# plaits_v50.net
KiCad netlist of a schematic drawn in EAGLE
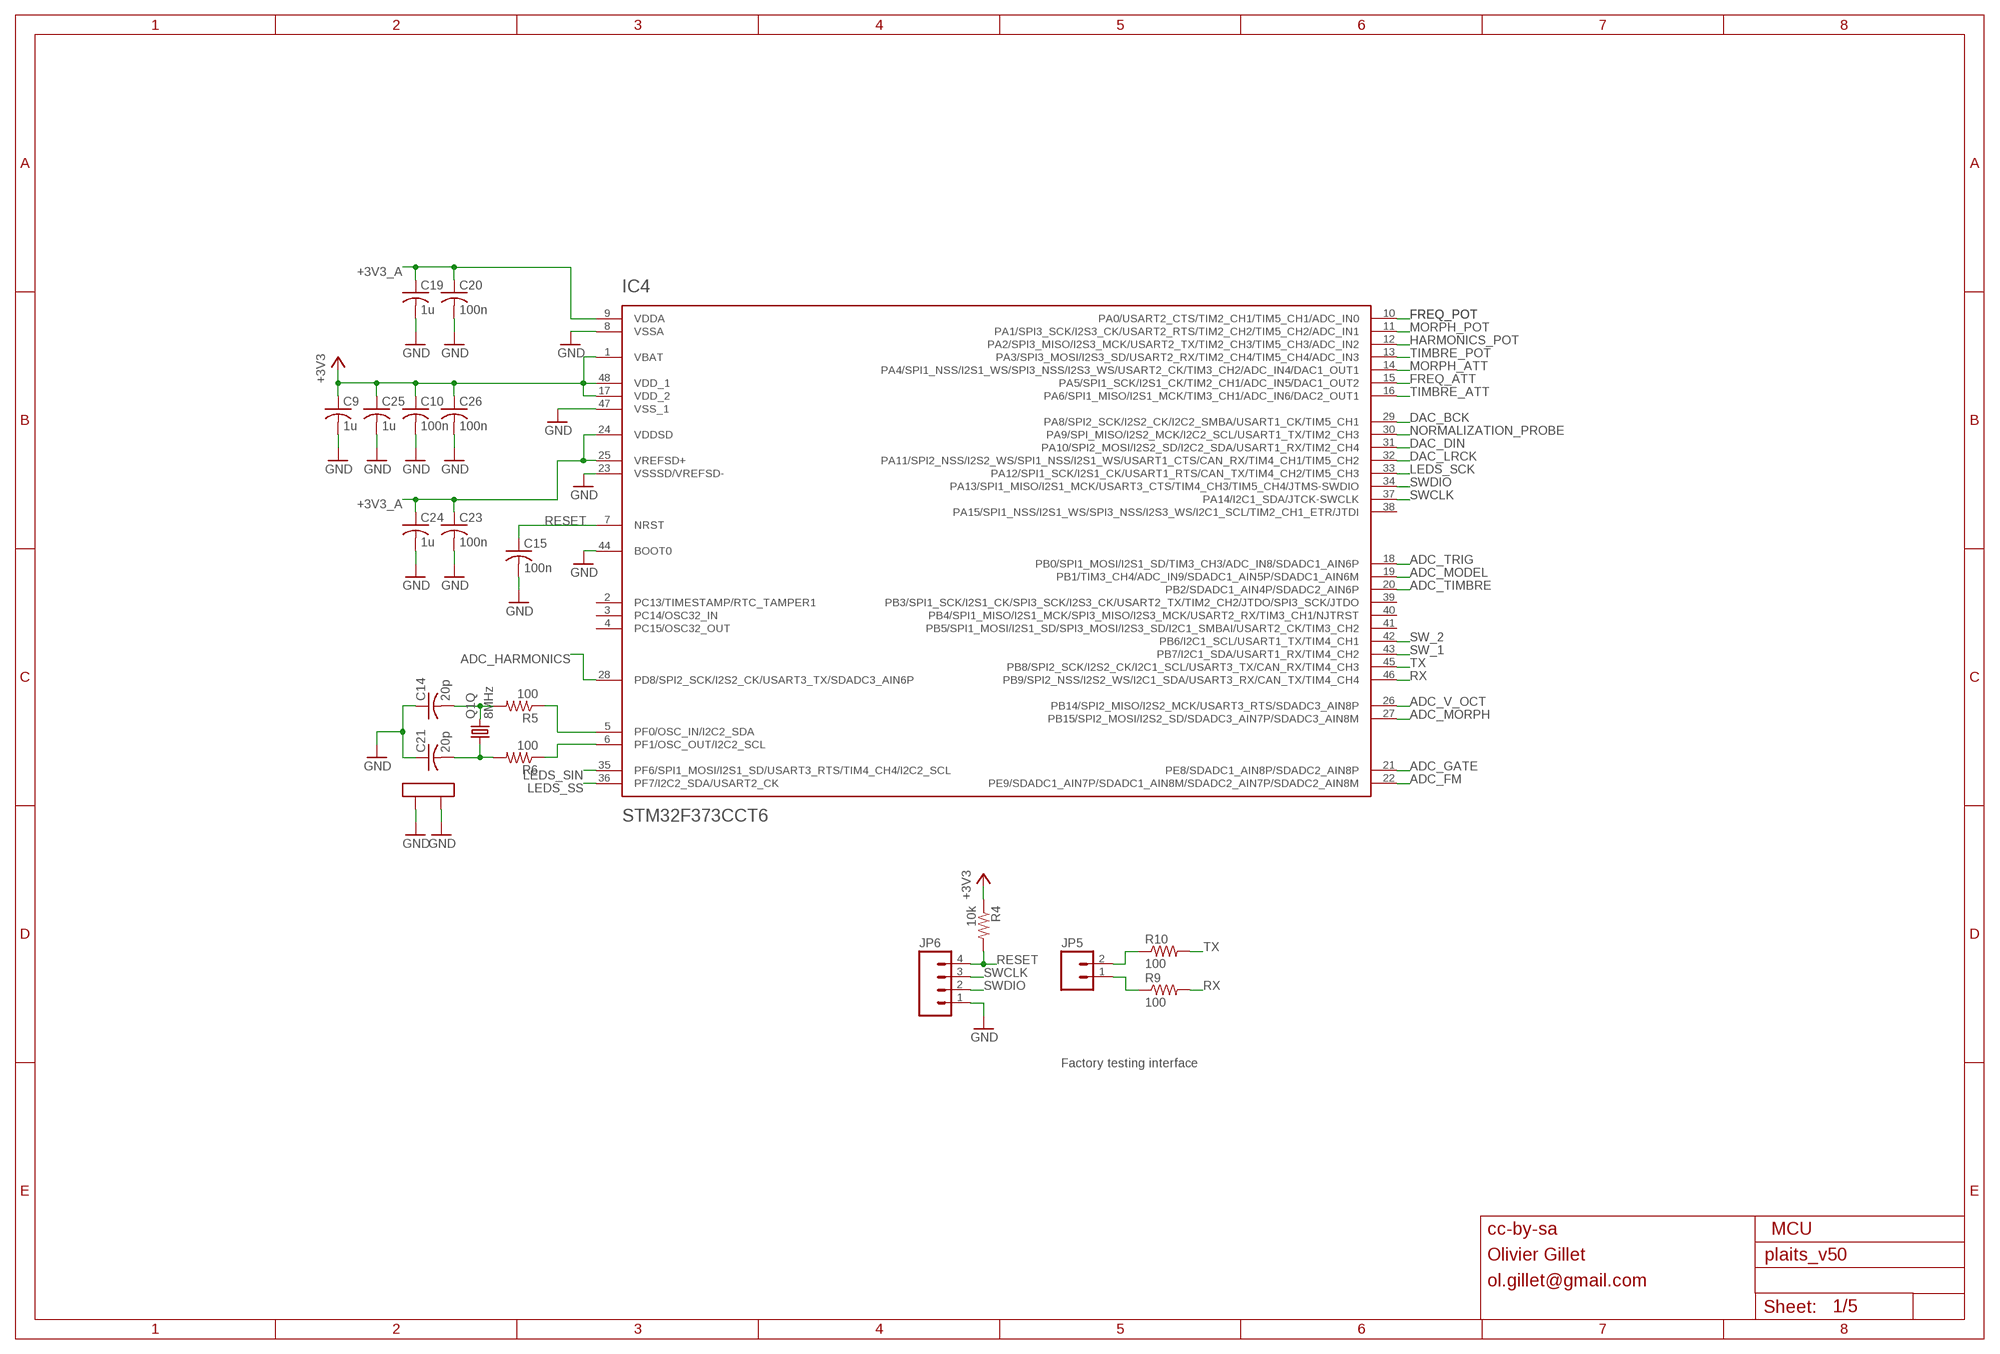
[diagram p0: schematic, sheet 1]
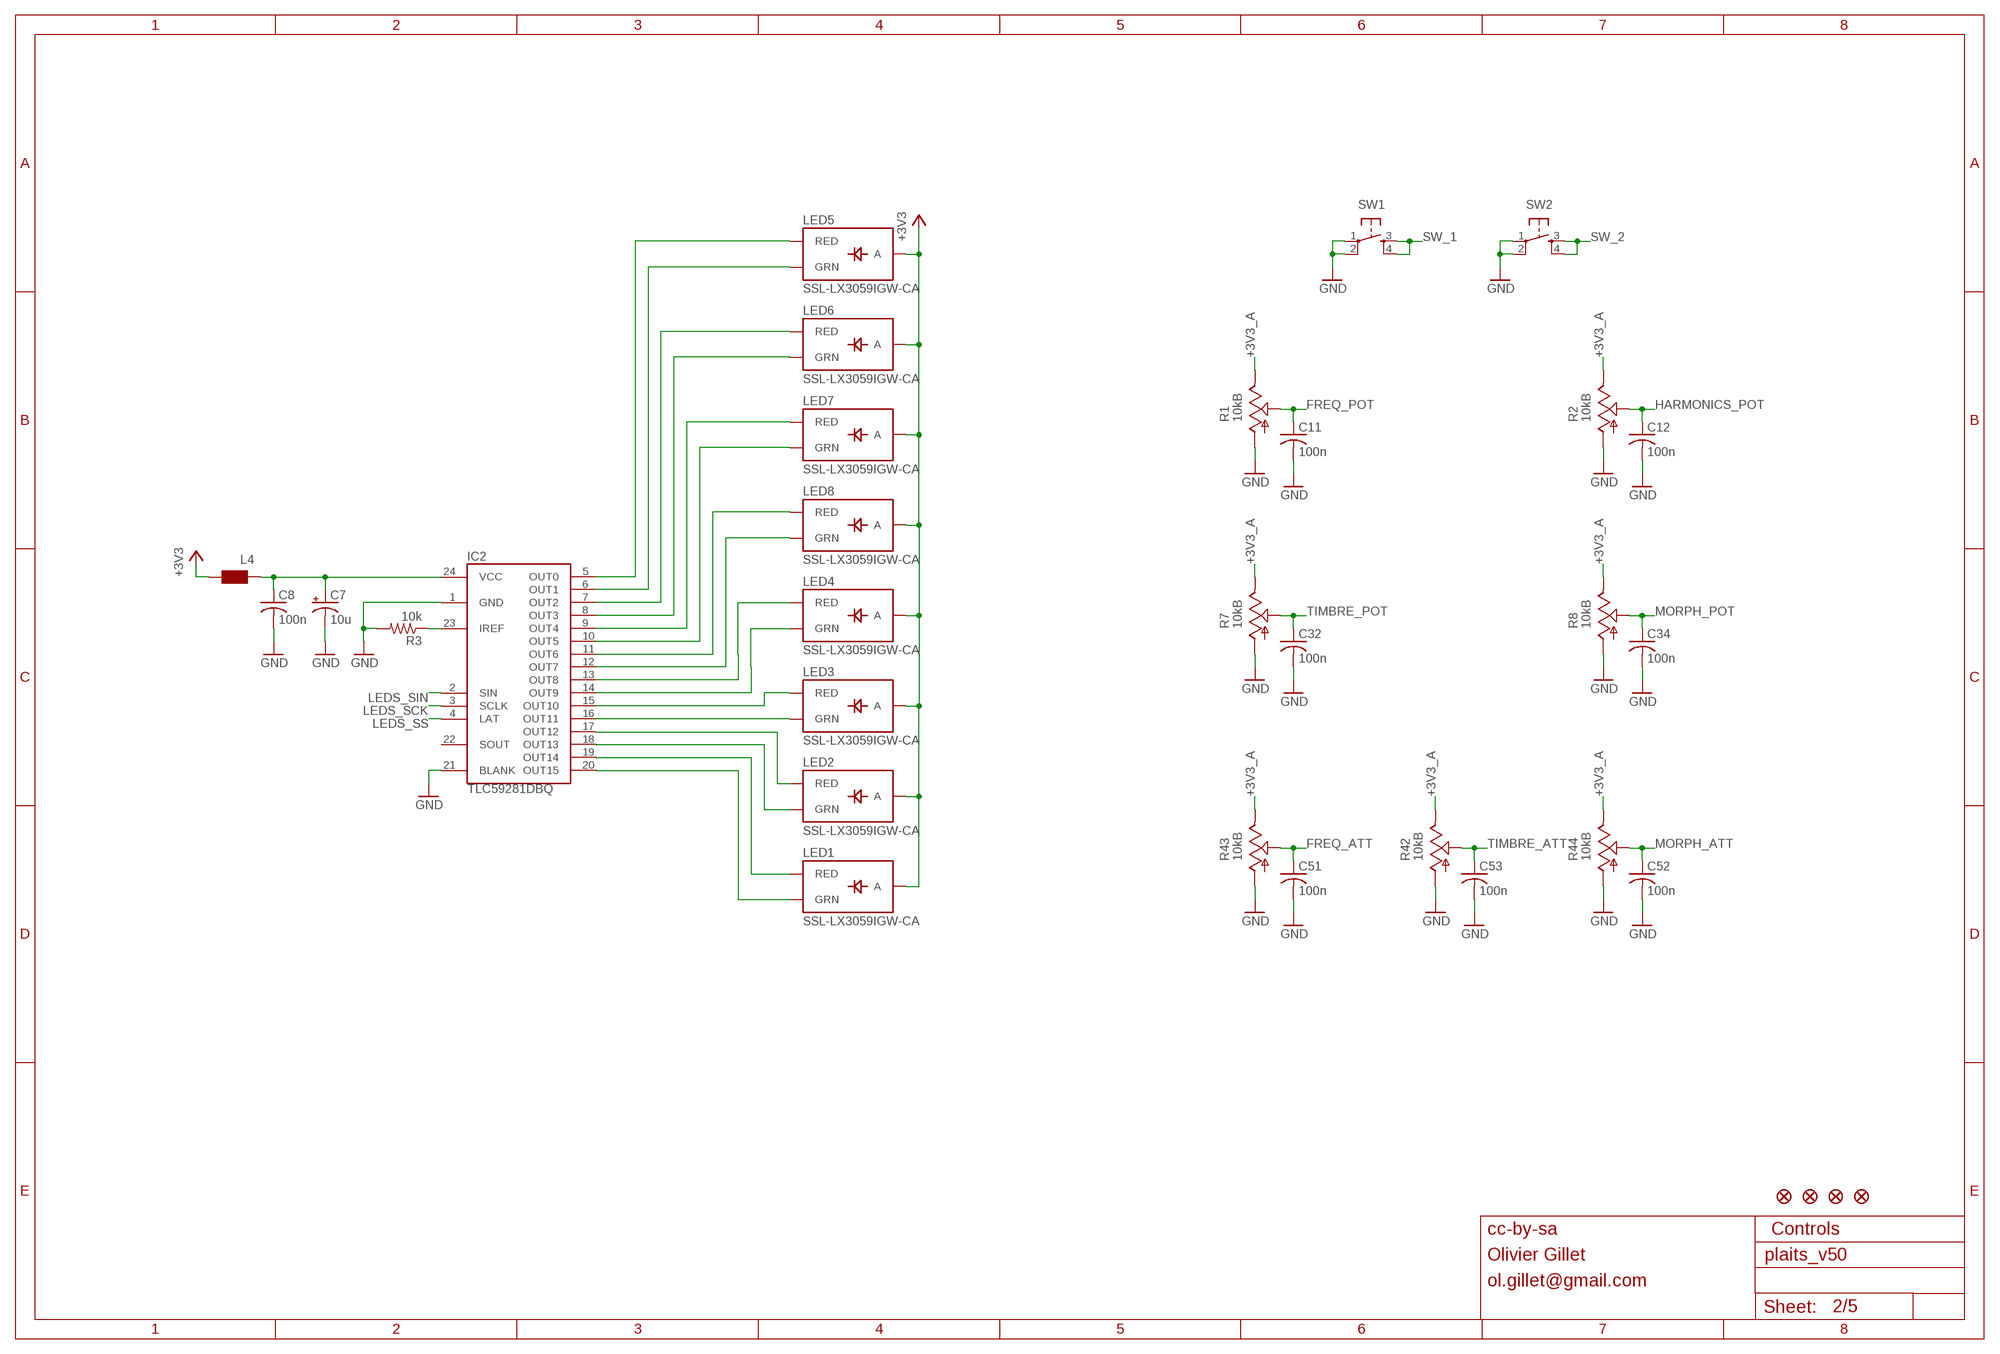
[diagram p1: schematic, sheet 2]
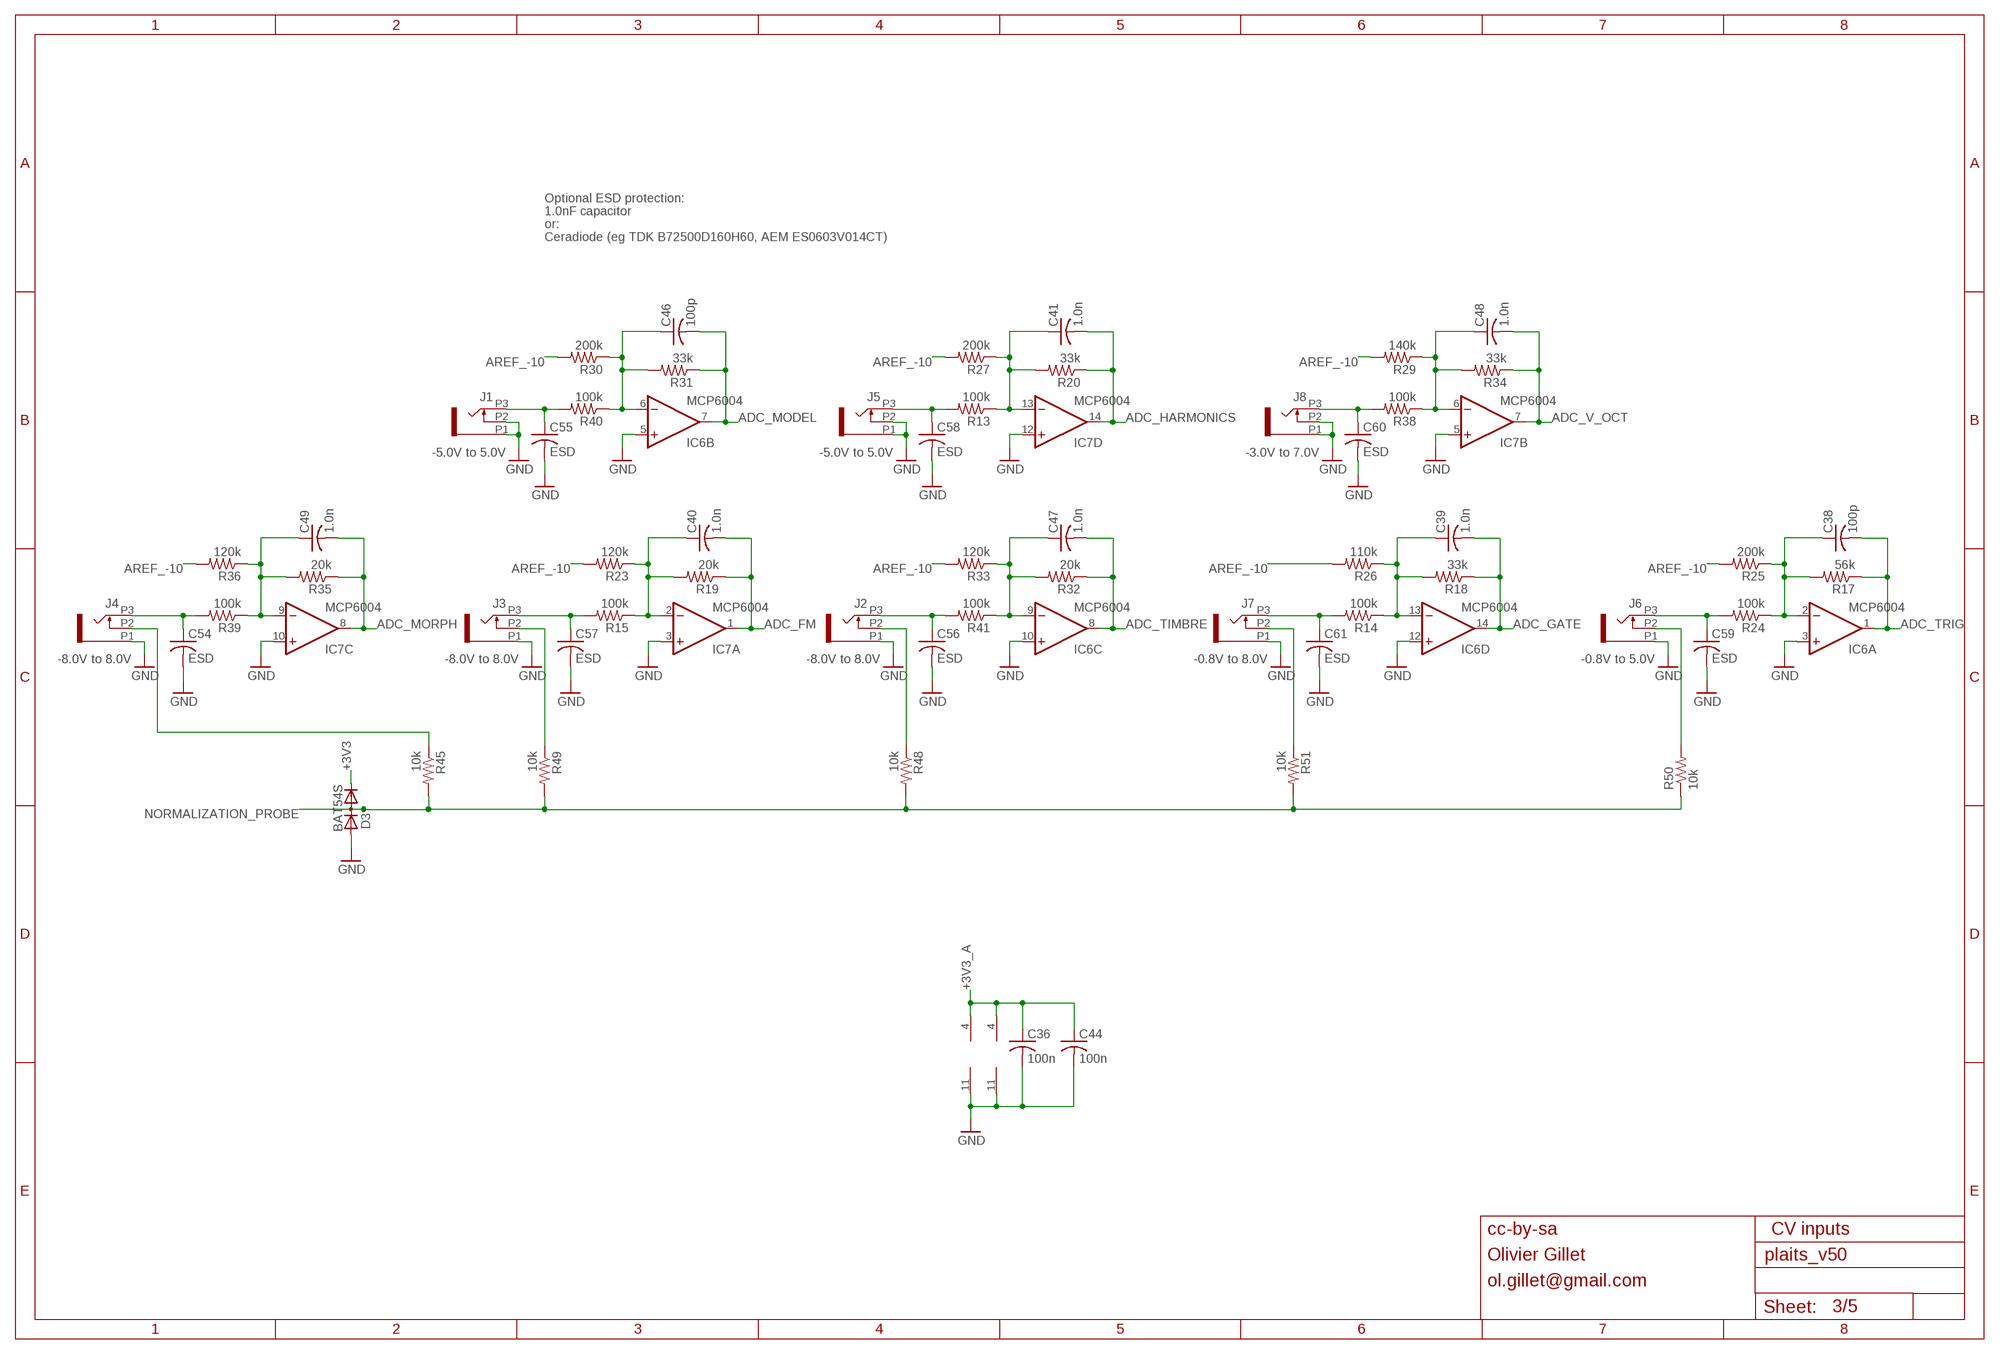
[diagram p2: schematic, sheet 3]
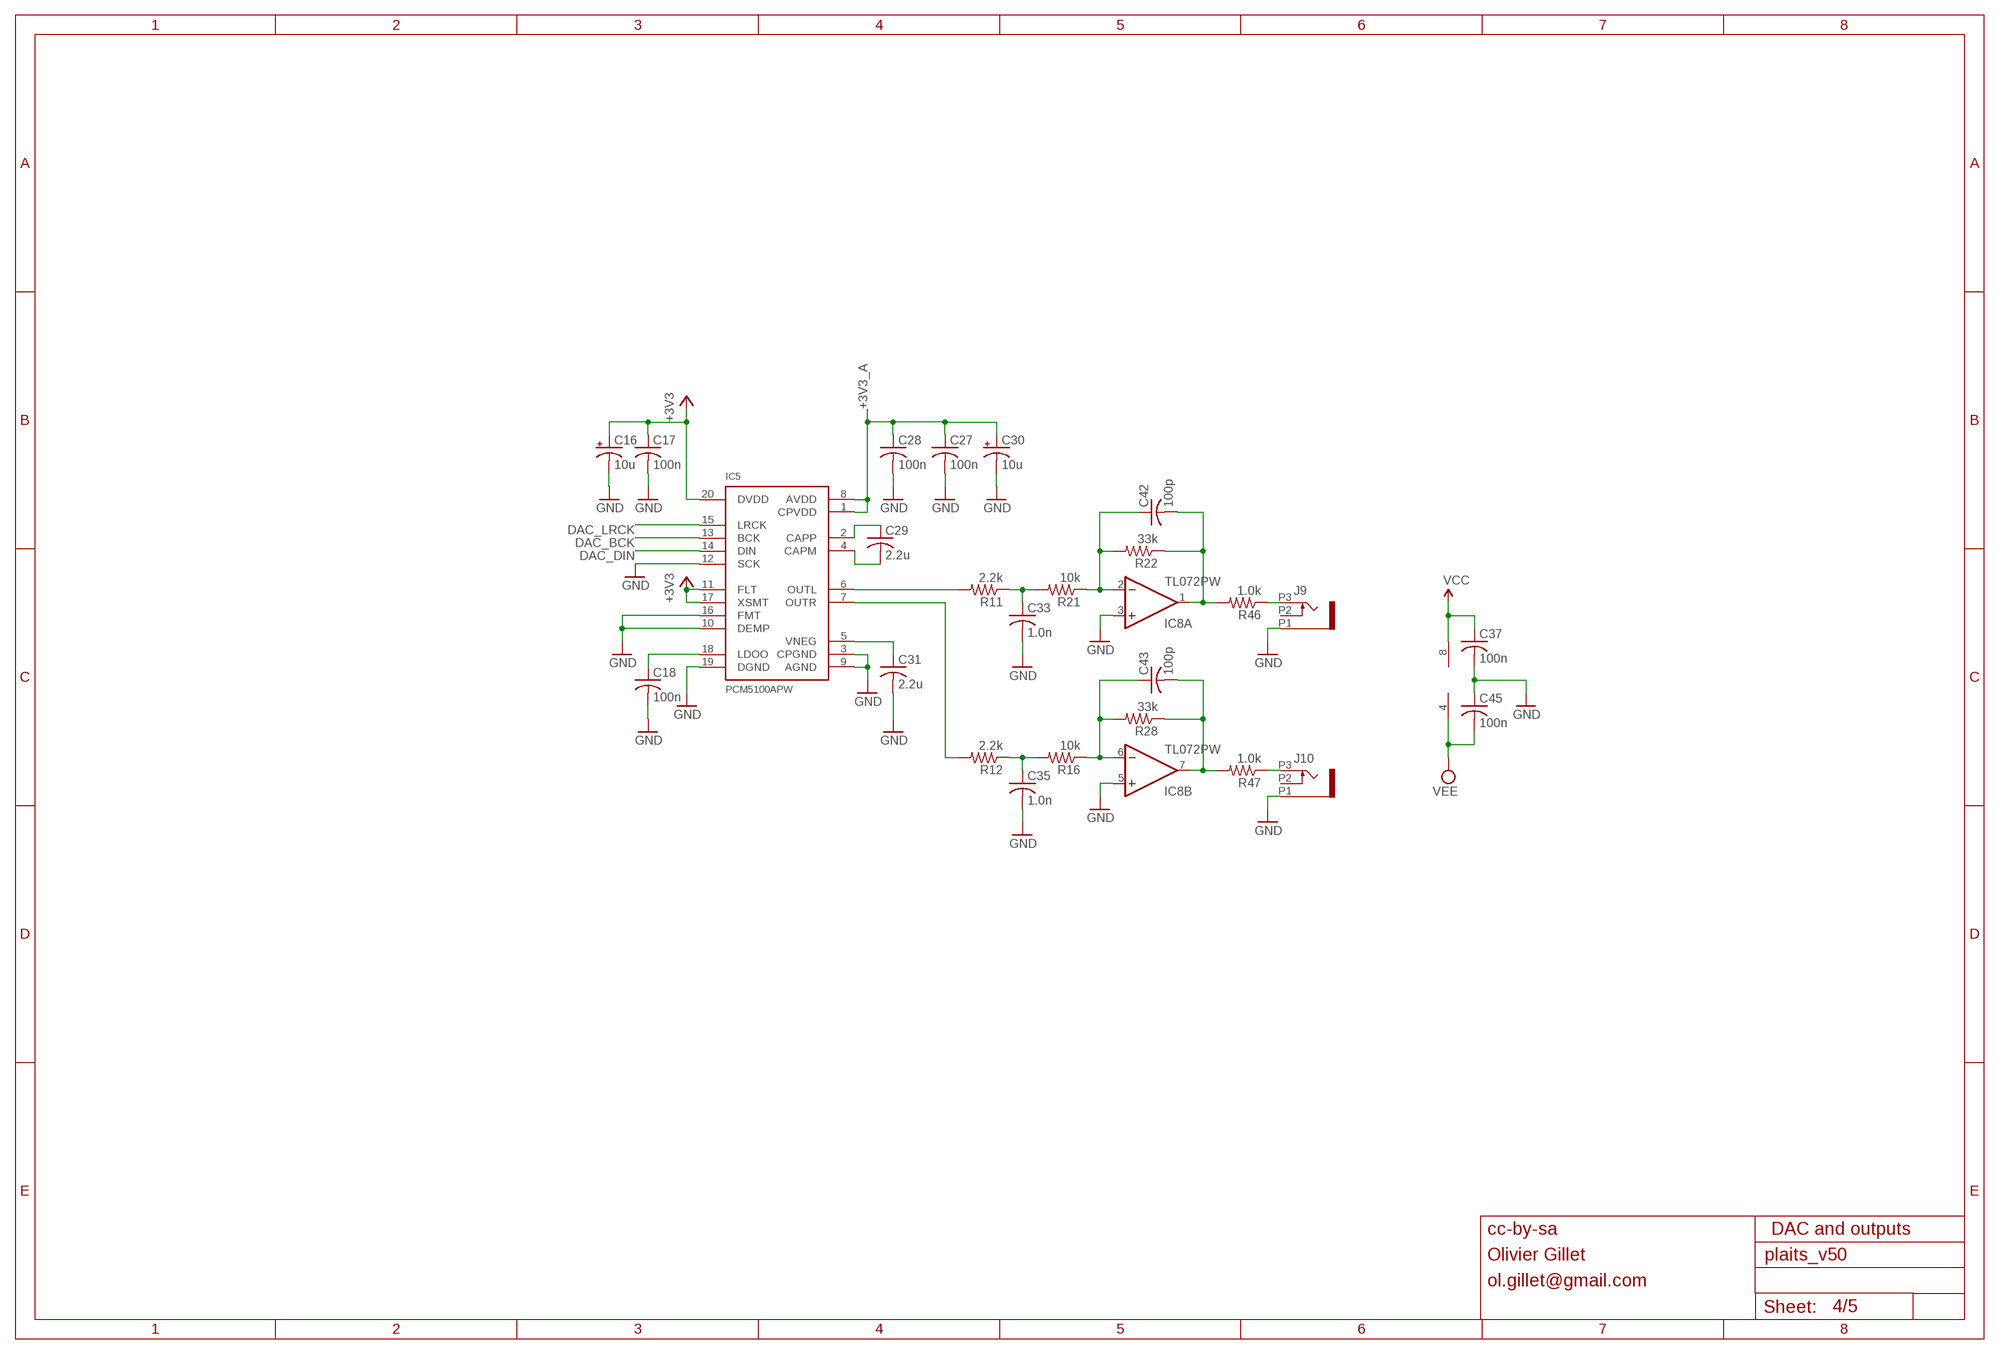
[diagram p3: schematic, sheet 4]
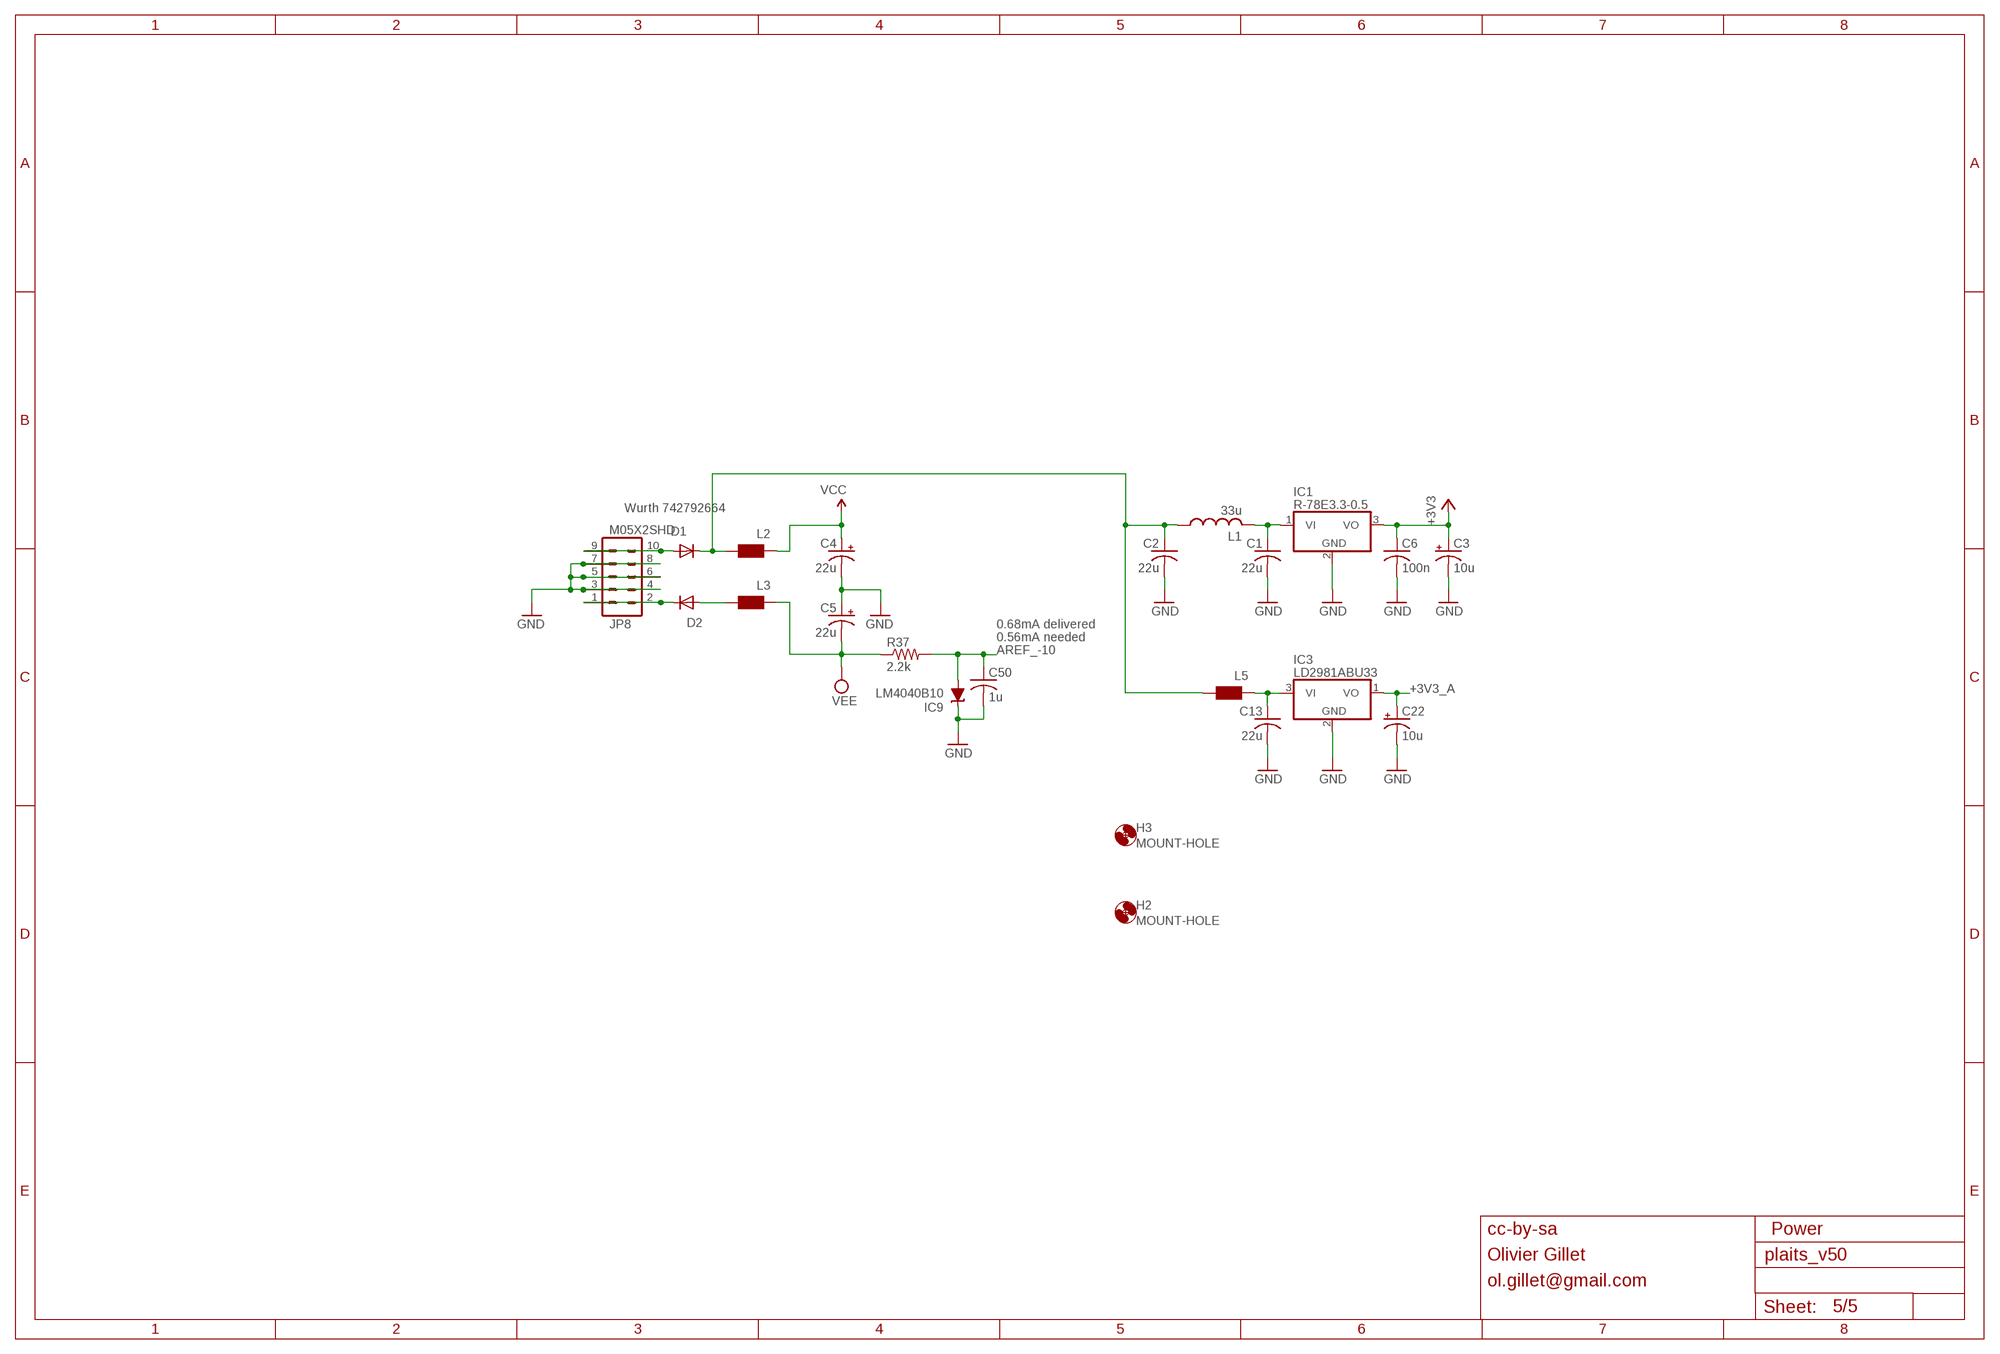
[diagram p4: schematic, sheet 5]

(export (version "E")
  (design (tool "Eeschema 10.0.6"))
  (components
    (comp (ref "C36")
      (value "100n")
      (footprint "eagle-import:C0603K")
      (libsource (lib "eagle-import") (part "rcl_334_C-USC0603K"))
    )
    (comp (ref "C38")
      (value "100p")
      (footprint "eagle-import:C0603K")
      (libsource (lib "eagle-import") (part "C-USC0603K"))
    )
    (comp (ref "C39")
      (value "1.0n")
      (footprint "eagle-import:C0603K")
      (libsource (lib "eagle-import") (part "C-USC0603K"))
    )
    (comp (ref "C40")
      (value "1.0n")
      (footprint "eagle-import:C0603K")
      (libsource (lib "eagle-import") (part "C-USC0603K"))
    )
    (comp (ref "C41")
      (value "1.0n")
      (footprint "eagle-import:C0603K")
      (libsource (lib "eagle-import") (part "C-USC0603K"))
    )
    (comp (ref "C44")
      (value "100n")
      (footprint "eagle-import:C0603K")
      (libsource (lib "eagle-import") (part "C-USC0603K"))
    )
    (comp (ref "C46")
      (value "100p")
      (footprint "eagle-import:C0603K")
      (libsource (lib "eagle-import") (part "C-USC0603K"))
    )
    (comp (ref "C47")
      (value "1.0n")
      (footprint "eagle-import:C0603K")
      (libsource (lib "eagle-import") (part "C-USC0603K"))
    )
    (comp (ref "C48")
      (value "1.0n")
      (footprint "eagle-import:C0603K")
      (libsource (lib "eagle-import") (part "C-USC0603K"))
    )
    (comp (ref "C49")
      (value "1.0n")
      (footprint "eagle-import:C0603K")
      (libsource (lib "eagle-import") (part "rcl_334_C-USC0603K"))
    )
    (comp (ref "C54")
      (value "ESD")
      (footprint "eagle-import:C0603K")
      (libsource (lib "eagle-import") (part "rcl_334_C-USC0603K"))
    )
    (comp (ref "C55")
      (value "ESD")
      (footprint "eagle-import:C0603K")
      (libsource (lib "eagle-import") (part "C-USC0603K"))
    )
    (comp (ref "C56")
      (value "ESD")
      (footprint "eagle-import:C0603")
      (libsource (lib "eagle-import") (part "C-USC0603"))
    )
    (comp (ref "C57")
      (value "ESD")
      (footprint "eagle-import:C0603K")
      (libsource (lib "eagle-import") (part "C-USC0603K"))
    )
    (comp (ref "C58")
      (value "ESD")
      (footprint "eagle-import:C0603K")
      (libsource (lib "eagle-import") (part "C-USC0603K"))
    )
    (comp (ref "C59")
      (value "ESD")
      (footprint "eagle-import:C0603K")
      (libsource (lib "eagle-import") (part "C-USC0603K"))
    )
    (comp (ref "C60")
      (value "ESD")
      (footprint "eagle-import:C0603K")
      (libsource (lib "eagle-import") (part "C-USC0603K"))
    )
    (comp (ref "C61")
      (value "ESD")
      (footprint "eagle-import:C0603K")
      (libsource (lib "eagle-import") (part "C-USC0603K"))
    )
    (comp (ref "D3")
      (value "BAT54S")
      (footprint "eagle-import:SOT23")
      (libsource (lib "eagle-import") (part "DIODE_2CACA-SOT23"))
    )
    (comp (ref "IC6")
      (value "MCP6004")
      (footprint "eagle-import:TSSOP14_065")
      (libsource (lib "eagle-import") (part "TL074PW"))
    )
    (comp (ref "IC7")
      (value "MCP6004")
      (footprint "eagle-import:TSSOP14_065")
      (libsource (lib "eagle-import") (part "TL074PW"))
    )
    (comp (ref "J1")
      (value "PJ301_THONKICONN6")
      (footprint "eagle-import:WQP_PJ_301M6")
      (libsource (lib "eagle-import") (part "PJ301_THONKICONN6"))
    )
    (comp (ref "J2")
      (value "PJ301_THONKICONN6")
      (footprint "eagle-import:WQP_PJ_301M6")
      (libsource (lib "eagle-import") (part "PJ301_THONKICONN6"))
    )
    (comp (ref "J3")
      (value "PJ301_THONKICONN6")
      (footprint "eagle-import:WQP_PJ_301M6")
      (libsource (lib "eagle-import") (part "PJ301_THONKICONN6"))
    )
    (comp (ref "J4")
      (value "PJ301_THONKICONN6")
      (footprint "eagle-import:WQP_PJ_301M6")
      (libsource (lib "eagle-import") (part "PJ301_THONKICONN6"))
    )
    (comp (ref "J5")
      (value "PJ301_THONKICONN6")
      (footprint "eagle-import:WQP_PJ_301M6")
      (libsource (lib "eagle-import") (part "PJ301_THONKICONN6"))
    )
    (comp (ref "J6")
      (value "PJ301_THONKICONN6")
      (footprint "eagle-import:WQP_PJ_301M6")
      (libsource (lib "eagle-import") (part "PJ301_THONKICONN6"))
    )
    (comp (ref "J7")
      (value "PJ301_THONKICONN6")
      (footprint "eagle-import:WQP_PJ_301M6")
      (libsource (lib "eagle-import") (part "PJ301_THONKICONN6"))
    )
    (comp (ref "J8")
      (value "PJ301_THONKICONN6")
      (footprint "eagle-import:WQP_PJ_301M6")
      (libsource (lib "eagle-import") (part "PJ301_THONKICONN6"))
    )
    (comp (ref "R13")
      (value "100k")
      (footprint "eagle-import:R0603")
      (libsource (lib "eagle-import") (part "R-US_R0603"))
    )
    (comp (ref "R14")
      (value "100k")
      (footprint "eagle-import:R0603")
      (libsource (lib "eagle-import") (part "R-US_R0603"))
    )
    (comp (ref "R15")
      (value "100k")
      (footprint "eagle-import:R0603")
      (libsource (lib "eagle-import") (part "R-US_R0603"))
    )
    (comp (ref "R17")
      (value "56k")
      (footprint "eagle-import:R0603")
      (libsource (lib "eagle-import") (part "R-US_R0603"))
    )
    (comp (ref "R18")
      (value "33k")
      (footprint "eagle-import:R0603")
      (libsource (lib "eagle-import") (part "R-US_R0603"))
    )
    (comp (ref "R19")
      (value "20k")
      (footprint "eagle-import:R0603")
      (libsource (lib "eagle-import") (part "R-US_R0603"))
    )
    (comp (ref "R20")
      (value "33k")
      (footprint "eagle-import:R0603")
      (libsource (lib "eagle-import") (part "R-US_R0603"))
    )
    (comp (ref "R23")
      (value "120k")
      (footprint "eagle-import:R0603")
      (libsource (lib "eagle-import") (part "R-US_R0603"))
    )
    (comp (ref "R24")
      (value "100k")
      (footprint "eagle-import:R0603")
      (libsource (lib "eagle-import") (part "R-US_R0603"))
    )
    (comp (ref "R25")
      (value "200k")
      (footprint "eagle-import:R0603")
      (libsource (lib "eagle-import") (part "R-US_R0603"))
    )
    (comp (ref "R26")
      (value "110k")
      (footprint "eagle-import:R0603")
      (libsource (lib "eagle-import") (part "R-US_R0603"))
    )
    (comp (ref "R27")
      (value "200k")
      (footprint "eagle-import:R0603")
      (libsource (lib "eagle-import") (part "R-US_R0603"))
    )
    (comp (ref "R29")
      (value "140k")
      (footprint "eagle-import:R0603")
      (libsource (lib "eagle-import") (part "R-US_R0603"))
    )
    (comp (ref "R30")
      (value "200k")
      (footprint "eagle-import:R0603")
      (libsource (lib "eagle-import") (part "R-US_R0603"))
    )
    (comp (ref "R31")
      (value "33k")
      (footprint "eagle-import:R0603")
      (libsource (lib "eagle-import") (part "R-US_R0603"))
    )
    (comp (ref "R32")
      (value "20k")
      (footprint "eagle-import:R0603")
      (libsource (lib "eagle-import") (part "R-US_R0603"))
    )
    (comp (ref "R33")
      (value "120k")
      (footprint "eagle-import:R0603")
      (libsource (lib "eagle-import") (part "R-US_R0603"))
    )
    (comp (ref "R34")
      (value "33k")
      (footprint "eagle-import:R0603")
      (libsource (lib "eagle-import") (part "R-US_R0603"))
    )
    (comp (ref "R35")
      (value "20k")
      (footprint "eagle-import:R0603")
      (libsource (lib "eagle-import") (part "R-US_R0603"))
    )
    (comp (ref "R36")
      (value "120k")
      (footprint "eagle-import:R0603")
      (libsource (lib "eagle-import") (part "R-US_R0603"))
    )
    (comp (ref "R38")
      (value "100k")
      (footprint "eagle-import:R0603")
      (libsource (lib "eagle-import") (part "rcl_334_R-US_R0603"))
    )
    (comp (ref "R39")
      (value "100k")
      (footprint "eagle-import:R0603")
      (libsource (lib "eagle-import") (part "rcl_334_R-US_R0603"))
    )
    (comp (ref "R40")
      (value "100k")
      (footprint "eagle-import:R0603")
      (libsource (lib "eagle-import") (part "R-US_R0603"))
    )
    (comp (ref "R41")
      (value "100k")
      (footprint "eagle-import:R0603")
      (libsource (lib "eagle-import") (part "R-US_R0603"))
    )
    (comp (ref "R45")
      (value "10k")
      (footprint "eagle-import:R0603")
      (libsource (lib "eagle-import") (part "R-US_R0603"))
    )
    (comp (ref "R48")
      (value "10k")
      (footprint "eagle-import:R0603")
      (libsource (lib "eagle-import") (part "rcl_334_R-US_R0603"))
    )
    (comp (ref "R49")
      (value "10k")
      (footprint "eagle-import:R0603")
      (libsource (lib "eagle-import") (part "R-US_R0603"))
    )
    (comp (ref "R50")
      (value "10k")
      (footprint "eagle-import:R0603")
      (libsource (lib "eagle-import") (part "R-US_R0603"))
    )
    (comp (ref "R51")
      (value "10k")
      (footprint "eagle-import:R0603")
      (libsource (lib "eagle-import") (part "R-US_R0603"))
    )
    (comp (ref "C9")
      (value "1u")
      (footprint "eagle-import:C0603K")
      (libsource (lib "eagle-import") (part "C-USC0603K"))
    )
    (comp (ref "C10")
      (value "100n")
      (footprint "eagle-import:C0603K")
      (libsource (lib "eagle-import") (part "C-USC0603K"))
    )
    (comp (ref "C14")
      (value "20p")
      (footprint "eagle-import:C0603K")
      (libsource (lib "eagle-import") (part "C-USC0603K"))
    )
    (comp (ref "C15")
      (value "100n")
      (footprint "eagle-import:C0603K")
      (libsource (lib "eagle-import") (part "C-USC0603K"))
    )
    (comp (ref "C19")
      (value "1u")
      (footprint "eagle-import:C0603K")
      (libsource (lib "eagle-import") (part "rcl_334_C-USC0603K"))
    )
    (comp (ref "C20")
      (value "100n")
      (footprint "eagle-import:C0603K")
      (libsource (lib "eagle-import") (part "C-USC0603K"))
    )
    (comp (ref "C21")
      (value "20p")
      (footprint "eagle-import:C0603K")
      (libsource (lib "eagle-import") (part "C-USC0603K"))
    )
    (comp (ref "C23")
      (value "100n")
      (footprint "eagle-import:C0603K")
      (libsource (lib "eagle-import") (part "C-USC0603K"))
    )
    (comp (ref "C24")
      (value "1u")
      (footprint "eagle-import:C0603K")
      (libsource (lib "eagle-import") (part "C-USC0603K"))
    )
    (comp (ref "C25")
      (value "1u")
      (footprint "eagle-import:C0603K")
      (libsource (lib "eagle-import") (part "C-USC0603K"))
    )
    (comp (ref "C26")
      (value "100n")
      (footprint "eagle-import:C0603K")
      (libsource (lib "eagle-import") (part "C-USC0603K"))
    )
    (comp (ref "IC4")
      (value "STM32F373CCT6")
      (footprint "eagle-import:LQFP48")
      (libsource (lib "eagle-import") (part "STM32F373C"))
    )
    (comp (ref "JP5")
      (value "M02PTH")
      (footprint "eagle-import:1X02")
      (libsource (lib "eagle-import") (part "M02PTH"))
    )
    (comp (ref "JP6")
      (value "M04PTH")
      (footprint "eagle-import:1X04")
      (libsource (lib "eagle-import") (part "M04PTH"))
    )
    (comp (ref "Q1")
      (value "8MHz")
      (footprint "eagle-import:CTS406")
      (libsource (lib "eagle-import") (part "CRYSTAL"))
    )
    (comp (ref "R4")
      (value "10k")
      (footprint "eagle-import:R0603")
      (libsource (lib "eagle-import") (part "R-US_R0603"))
    )
    (comp (ref "R5")
      (value "100")
      (footprint "eagle-import:R0603")
      (libsource (lib "eagle-import") (part "rcl_334_R-US_R0603"))
    )
    (comp (ref "R6")
      (value "100")
      (footprint "eagle-import:R0603")
      (libsource (lib "eagle-import") (part "R-US_R0603"))
    )
    (comp (ref "R9")
      (value "100")
      (footprint "eagle-import:R0603")
      (libsource (lib "eagle-import") (part "R-US_R0603"))
    )
    (comp (ref "R10")
      (value "100")
      (footprint "eagle-import:R0603")
      (libsource (lib "eagle-import") (part "R-US_R0603"))
    )
    (comp (ref "C7")
      (value "10u")
      (footprint "eagle-import:PANASONIC_A")
      (libsource (lib "eagle-import") (part "CPOL-USA"))
    )
    (comp (ref "C8")
      (value "100n")
      (footprint "eagle-import:C0603K")
      (libsource (lib "eagle-import") (part "rcl_334_C-USC0603K"))
    )
    (comp (ref "C11")
      (value "100n")
      (footprint "eagle-import:C0603K")
      (libsource (lib "eagle-import") (part "C-USC0603K"))
    )
    (comp (ref "C12")
      (value "100n")
      (footprint "eagle-import:C0603K")
      (libsource (lib "eagle-import") (part "C-USC0603K"))
    )
    (comp (ref "C32")
      (value "100n")
      (footprint "eagle-import:C0603K")
      (libsource (lib "eagle-import") (part "C-USC0603K"))
    )
    (comp (ref "C34")
      (value "100n")
      (footprint "eagle-import:C0603K")
      (libsource (lib "eagle-import") (part "C-USC0603K"))
    )
    (comp (ref "C51")
      (value "100n")
      (footprint "eagle-import:C0603K")
      (libsource (lib "eagle-import") (part "C-USC0603K"))
    )
    (comp (ref "C52")
      (value "100n")
      (footprint "eagle-import:C0603K")
      (libsource (lib "eagle-import") (part "C-USC0603K"))
    )
    (comp (ref "C53")
      (value "100n")
      (footprint "eagle-import:C0603K")
      (libsource (lib "eagle-import") (part "C-USC0603K"))
    )
    (comp (ref "IC2")
      (value "TLC59281DBQ")
      (footprint "eagle-import:TSSOP24_0635")
      (libsource (lib "eagle-import") (part "TLC59281DBQ"))
    )
    (comp (ref "JP1")
      (value "FIDUCIAL1X2")
      (footprint "eagle-import:FIDUCIAL-1X2")
      (libsource (lib "eagle-import") (part "FIDUCIAL1X2"))
    )
    (comp (ref "JP2")
      (value "FIDUCIAL1X2")
      (footprint "eagle-import:FIDUCIAL-1X2")
      (libsource (lib "eagle-import") (part "FIDUCIAL1X2"))
    )
    (comp (ref "JP3")
      (value "FIDUCIAL1X2")
      (footprint "eagle-import:FIDUCIAL-1X2")
      (libsource (lib "eagle-import") (part "FIDUCIAL1X2"))
    )
    (comp (ref "JP4")
      (value "FIDUCIAL1X2")
      (footprint "eagle-import:FIDUCIAL-1X2")
      (libsource (lib "eagle-import") (part "FIDUCIAL1X2"))
    )
    (comp (ref "L4")
      (value "WE-CBF_0603")
      (footprint "eagle-import:0603")
      (libsource (lib "eagle-import") (part "WE-CBF_0603"))
    )
    (comp (ref "LED1")
      (value "SSL-LX3059IGW-CA")
      (footprint "eagle-import:LED-BICOLOR-THROUGHHOLE-LUMEX")
      (libsource (lib "eagle-import") (part "LED-BICOLOR-THROUGHHOLE-CA"))
    )
    (comp (ref "LED2")
      (value "SSL-LX3059IGW-CA")
      (footprint "eagle-import:LED-BICOLOR-THROUGHHOLE-LUMEX")
      (libsource (lib "eagle-import") (part "LED-BICOLOR-THROUGHHOLE-CA"))
    )
    (comp (ref "LED3")
      (value "SSL-LX3059IGW-CA")
      (footprint "eagle-import:LED-BICOLOR-THROUGHHOLE-LUMEX")
      (libsource (lib "eagle-import") (part "LED-BICOLOR-THROUGHHOLE-CA"))
    )
    (comp (ref "LED4")
      (value "SSL-LX3059IGW-CA")
      (footprint "eagle-import:LED-BICOLOR-THROUGHHOLE-LUMEX")
      (libsource (lib "eagle-import") (part "LED-BICOLOR-THROUGHHOLE-CA"))
    )
    (comp (ref "LED5")
      (value "SSL-LX3059IGW-CA")
      (footprint "eagle-import:LED-BICOLOR-THROUGHHOLE-LUMEX")
      (libsource (lib "eagle-import") (part "LED-BICOLOR-THROUGHHOLE-CA"))
    )
    (comp (ref "LED6")
      (value "SSL-LX3059IGW-CA")
      (footprint "eagle-import:LED-BICOLOR-THROUGHHOLE-LUMEX")
      (libsource (lib "eagle-import") (part "LED-BICOLOR-THROUGHHOLE-CA"))
    )
    (comp (ref "LED7")
      (value "SSL-LX3059IGW-CA")
      (footprint "eagle-import:LED-BICOLOR-THROUGHHOLE-LUMEX")
      (libsource (lib "eagle-import") (part "LED-BICOLOR-THROUGHHOLE-CA"))
    )
    (comp (ref "LED8")
      (value "SSL-LX3059IGW-CA")
      (footprint "eagle-import:LED-BICOLOR-THROUGHHOLE-LUMEX")
      (libsource (lib "eagle-import") (part "LED-BICOLOR-THROUGHHOLE-CA"))
    )
    (comp (ref "R1")
      (value "10kB")
      (footprint "eagle-import:ALPS_POT_VERTICAL_PS")
      (libsource (lib "eagle-import") (part "POT_USVERTICAL_PS"))
    )
    (comp (ref "R2")
      (value "10kB")
      (footprint "eagle-import:ALPS_POT_VERTICAL_PS")
      (libsource (lib "eagle-import") (part "POT_USVERTICAL_PS"))
    )
    (comp (ref "R3")
      (value "10k")
      (footprint "eagle-import:R0603")
      (libsource (lib "eagle-import") (part "rcl_334_R-US_R0603"))
    )
    (comp (ref "R7")
      (value "10kB")
      (footprint "eagle-import:ALPS_POT_VERTICAL_PS")
      (libsource (lib "eagle-import") (part "POT_USVERTICAL_PS"))
    )
    (comp (ref "R8")
      (value "10kB")
      (footprint "eagle-import:ALPS_POT_VERTICAL_PS")
      (libsource (lib "eagle-import") (part "POT_USVERTICAL_PS"))
    )
    (comp (ref "R42")
      (value "10kB")
      (footprint "eagle-import:ALPS_POT_VERTICAL")
      (libsource (lib "eagle-import") (part "POT_USVERTICAL"))
    )
    (comp (ref "R43")
      (value "10kB")
      (footprint "eagle-import:ALPS_POT_VERTICAL")
      (libsource (lib "eagle-import") (part "POT_USVERTICAL"))
    )
    (comp (ref "R44")
      (value "10kB")
      (footprint "eagle-import:ALPS_POT_VERTICAL")
      (libsource (lib "eagle-import") (part "POT_USVERTICAL"))
    )
    (comp (ref "SW1")
      (value "TAC_SWITCHPTH")
      (footprint "eagle-import:TACTILE-PTH")
      (libsource (lib "eagle-import") (part "TAC_SWITCHPTH"))
    )
    (comp (ref "SW2")
      (value "TAC_SWITCHPTH")
      (footprint "eagle-import:TACTILE-PTH")
      (libsource (lib "eagle-import") (part "TAC_SWITCHPTH"))
    )
    (comp (ref "C1")
      (value "22u")
      (footprint "eagle-import:C1206")
      (libsource (lib "eagle-import") (part "C-USC1206"))
    )
    (comp (ref "C2")
      (value "22u")
      (footprint "eagle-import:C1206")
      (libsource (lib "eagle-import") (part "C-USC1206"))
    )
    (comp (ref "C3")
      (value "10u")
      (footprint "eagle-import:PANASONIC_A")
      (libsource (lib "eagle-import") (part "CPOL-USA"))
    )
    (comp (ref "C4")
      (value "22u")
      (footprint "eagle-import:PANASONIC_B")
      (libsource (lib "eagle-import") (part "CPOL-USB"))
    )
    (comp (ref "C5")
      (value "22u")
      (footprint "eagle-import:PANASONIC_B")
      (libsource (lib "eagle-import") (part "CPOL-USB"))
    )
    (comp (ref "C6")
      (value "100n")
      (footprint "eagle-import:C0603K")
      (libsource (lib "eagle-import") (part "rcl_334_C-USC0603K"))
    )
    (comp (ref "C13")
      (value "22u")
      (footprint "eagle-import:C1206")
      (libsource (lib "eagle-import") (part "C-USC1206"))
    )
    (comp (ref "C22")
      (value "10u")
      (footprint "eagle-import:PANASONIC_A")
      (libsource (lib "eagle-import") (part "CPOL-USA"))
    )
    (comp (ref "C50")
      (value "1u")
      (footprint "eagle-import:C0603K")
      (libsource (lib "eagle-import") (part "rcl_334_C-USC0603K"))
    )
    (comp (ref "D1")
      (value "1N5819HW")
      (footprint "eagle-import:SOD123")
      (libsource (lib "eagle-import") (part "DIODE-SOD123"))
    )
    (comp (ref "D2")
      (value "1N5819HW")
      (footprint "eagle-import:SOD123")
      (libsource (lib "eagle-import") (part "DIODE-SOD123"))
    )
    (comp (ref "H2")
      (value "MOUNT-HOLE")
      (footprint "eagle-import:3,0TINY")
      (libsource (lib "eagle-import") (part "MOUNT-HOLE3.0TINY"))
    )
    (comp (ref "H3")
      (value "MOUNT-HOLE")
      (footprint "eagle-import:3,0TINY")
      (libsource (lib "eagle-import") (part "MOUNT-HOLE3.0TINY"))
    )
    (comp (ref "IC1")
      (value "R-78E3.3-0.5")
      (footprint "eagle-import:WE78")
      (libsource (lib "eagle-import") (part "WE173950378"))
    )
    (comp (ref "IC3")
      (value "LD2981ABU33")
      (footprint "eagle-import:SOT89")
      (libsource (lib "eagle-import") (part "LD2981ABU"))
    )
    (comp (ref "IC9")
      (value "LM4040B10")
      (footprint "eagle-import:DBZ_R-PDSO-G3")
      (libsource (lib "eagle-import") (part "LM4041DBZB12"))
    )
    (comp (ref "JP8")
      (value "M05X2SHD")
      (footprint "eagle-import:2X5-SHROUDED")
      (libsource (lib "eagle-import") (part "M05X2SHD"))
    )
    (comp (ref "L1")
      (value "33u")
      (footprint "eagle-import:L2012C")
      (libsource (lib "eagle-import") (part "L-USL2012C"))
    )
    (comp (ref "L2")
      (value "WE-CBF_0603")
      (footprint "eagle-import:0603")
      (libsource (lib "eagle-import") (part "WE-CBF_0603"))
    )
    (comp (ref "L3")
      (value "WE-CBF_0603")
      (footprint "eagle-import:0603")
      (libsource (lib "eagle-import") (part "WE-CBF_0603"))
    )
    (comp (ref "L5")
      (value "WE-CBF_0603")
      (footprint "eagle-import:0603")
      (libsource (lib "eagle-import") (part "WE-CBF_0603"))
    )
    (comp (ref "R37")
      (value "2.2k")
      (footprint "eagle-import:R0603")
      (libsource (lib "eagle-import") (part "rcl_334_R-US_R0603"))
    )
    (comp (ref "C16")
      (value "10u")
      (footprint "eagle-import:PANASONIC_A")
      (libsource (lib "eagle-import") (part "CPOL-USA"))
    )
    (comp (ref "C17")
      (value "100n")
      (footprint "eagle-import:C0603K")
      (libsource (lib "eagle-import") (part "rcl_334_C-USC0603K"))
    )
    (comp (ref "C18")
      (value "100n")
      (footprint "eagle-import:C0603K")
      (libsource (lib "eagle-import") (part "rcl_334_C-USC0603K"))
    )
    (comp (ref "C27")
      (value "100n")
      (footprint "eagle-import:C0603K")
      (libsource (lib "eagle-import") (part "rcl_334_C-USC0603K"))
    )
    (comp (ref "C28")
      (value "100n")
      (footprint "eagle-import:C0603K")
      (libsource (lib "eagle-import") (part "C-USC0603K"))
    )
    (comp (ref "C29")
      (value "2.2u")
      (footprint "eagle-import:C0805")
      (libsource (lib "eagle-import") (part "C-USC0805"))
    )
    (comp (ref "C30")
      (value "10u")
      (footprint "eagle-import:PANASONIC_A")
      (libsource (lib "eagle-import") (part "CPOL-USA"))
    )
    (comp (ref "C31")
      (value "2.2u")
      (footprint "eagle-import:C0805")
      (libsource (lib "eagle-import") (part "C-USC0805"))
    )
    (comp (ref "C33")
      (value "1.0n")
      (footprint "eagle-import:C0603K")
      (libsource (lib "eagle-import") (part "C-USC0603K"))
    )
    (comp (ref "C35")
      (value "1.0n")
      (footprint "eagle-import:C0603K")
      (libsource (lib "eagle-import") (part "C-USC0603K"))
    )
    (comp (ref "C37")
      (value "100n")
      (footprint "eagle-import:C0603K")
      (libsource (lib "eagle-import") (part "C-USC0603K"))
    )
    (comp (ref "C42")
      (value "100p")
      (footprint "eagle-import:C0603K")
      (libsource (lib "eagle-import") (part "C-USC0603K"))
    )
    (comp (ref "C43")
      (value "100p")
      (footprint "eagle-import:C0603K")
      (libsource (lib "eagle-import") (part "C-USC0603K"))
    )
    (comp (ref "C45")
      (value "100n")
      (footprint "eagle-import:C0603K")
      (libsource (lib "eagle-import") (part "C-USC0603K"))
    )
    (comp (ref "IC5")
      (value "PCM5100APW")
      (footprint "eagle-import:SSOP20")
      (libsource (lib "eagle-import") (part "PCM5100PW"))
    )
    (comp (ref "IC8")
      (value "TL072PW")
      (footprint "eagle-import:TSSOP08")
      (libsource (lib "eagle-import") (part "TL072PW"))
    )
    (comp (ref "J9")
      (value "PJ301_THONKICONN6")
      (footprint "eagle-import:WQP_PJ_301M6")
      (libsource (lib "eagle-import") (part "PJ301_THONKICONN6"))
    )
    (comp (ref "J10")
      (value "PJ301_THONKICONN6")
      (footprint "eagle-import:WQP_PJ_301M6")
      (libsource (lib "eagle-import") (part "PJ301_THONKICONN6"))
    )
    (comp (ref "R11")
      (value "2.2k")
      (footprint "eagle-import:R0603")
      (libsource (lib "eagle-import") (part "R-US_R0603"))
    )
    (comp (ref "R12")
      (value "2.2k")
      (footprint "eagle-import:R0603")
      (libsource (lib "eagle-import") (part "R-US_R0603"))
    )
    (comp (ref "R16")
      (value "10k")
      (footprint "eagle-import:R0603")
      (libsource (lib "eagle-import") (part "R-US_R0603"))
    )
    (comp (ref "R21")
      (value "10k")
      (footprint "eagle-import:R0603")
      (libsource (lib "eagle-import") (part "R-US_R0603"))
    )
    (comp (ref "R22")
      (value "33k")
      (footprint "eagle-import:R0603")
      (libsource (lib "eagle-import") (part "rcl_334_R-US_R0603"))
    )
    (comp (ref "R28")
      (value "33k")
      (footprint "eagle-import:R0603")
      (libsource (lib "eagle-import") (part "R-US_R0603"))
    )
    (comp (ref "R46")
      (value "1.0k")
      (footprint "eagle-import:R0603")
      (libsource (lib "eagle-import") (part "R-US_R0603"))
    )
    (comp (ref "R47")
      (value "1.0k")
      (footprint "eagle-import:R0603")
      (libsource (lib "eagle-import") (part "R-US_R0603"))
    )
  )
  (nets
    (net (code "1") (name "+3V3") (class "Default")
      (node (ref "C10") (pin "1") (pinfunction "1_1") (pintype "passive"))
      (node (ref "C16") (pin "+") (pinfunction "+_+") (pintype "passive"))
      (node (ref "C17") (pin "1") (pinfunction "1_1") (pintype "passive"))
      (node (ref "C25") (pin "1") (pinfunction "1_1") (pintype "passive"))
      (node (ref "C26") (pin "1") (pinfunction "1_1") (pintype "passive"))
      (node (ref "C3") (pin "+") (pinfunction "+_+") (pintype "passive"))
      (node (ref "C6") (pin "1") (pinfunction "1_1") (pintype "passive"))
      (node (ref "C9") (pin "1") (pinfunction "1_1") (pintype "passive"))
      (node (ref "D3") (pin "2") (pinfunction "C_2") (pintype "passive"))
      (node (ref "IC1") (pin "3") (pinfunction "VO_3") (pintype "passive"))
      (node (ref "IC4") (pin "1") (pinfunction "VBAT_1") (pintype "power_in"))
      (node (ref "IC4") (pin "17") (pinfunction "VDD_2_17") (pintype "power_in"))
      (node (ref "IC4") (pin "48") (pinfunction "VDD_1_48") (pintype "power_in"))
      (node (ref "IC5") (pin "11") (pinfunction "FLT_11") (pintype "input"))
      (node (ref "IC5") (pin "17") (pinfunction "XSMT_17") (pintype "input"))
      (node (ref "IC5") (pin "20") (pinfunction "DVDD_20") (pintype "power_in"))
      (node (ref "L4") (pin "2") (pinfunction "2_2") (pintype "passive"))
      (node (ref "LED1") (pin "A") (pinfunction "A_A") (pintype "bidirectional"))
      (node (ref "LED2") (pin "A") (pinfunction "A_A") (pintype "bidirectional"))
      (node (ref "LED3") (pin "A") (pinfunction "A_A") (pintype "bidirectional"))
      (node (ref "LED4") (pin "A") (pinfunction "A_A") (pintype "bidirectional"))
      (node (ref "LED5") (pin "A") (pinfunction "A_A") (pintype "bidirectional"))
      (node (ref "LED6") (pin "A") (pinfunction "A_A") (pintype "bidirectional"))
      (node (ref "LED7") (pin "A") (pinfunction "A_A") (pintype "bidirectional"))
      (node (ref "LED8") (pin "A") (pinfunction "A_A") (pintype "bidirectional"))
      (node (ref "R4") (pin "1") (pinfunction "1_1") (pintype "passive"))
    )
    (net (code "2") (name "+3V3_A") (class "Default")
      (node (ref "C19") (pin "1") (pinfunction "1_1") (pintype "passive"))
      (node (ref "C20") (pin "1") (pinfunction "1_1") (pintype "passive"))
      (node (ref "C22") (pin "+") (pinfunction "+_+") (pintype "passive"))
      (node (ref "C23") (pin "1") (pinfunction "1_1") (pintype "passive"))
      (node (ref "C24") (pin "1") (pinfunction "1_1") (pintype "passive"))
      (node (ref "C27") (pin "1") (pinfunction "1_1") (pintype "passive"))
      (node (ref "C28") (pin "1") (pinfunction "1_1") (pintype "passive"))
      (node (ref "C30") (pin "+") (pinfunction "+_+") (pintype "passive"))
      (node (ref "C36") (pin "1") (pinfunction "1_1") (pintype "passive"))
      (node (ref "C44") (pin "1") (pinfunction "1_1") (pintype "passive"))
      (node (ref "IC3") (pin "1") (pinfunction "VO_1") (pintype "passive"))
      (node (ref "IC4") (pin "24") (pinfunction "VDDSD_24") (pintype "power_in"))
      (node (ref "IC4") (pin "25") (pinfunction "VREFSD+_25") (pintype "power_in"))
      (node (ref "IC4") (pin "9") (pinfunction "VDDA_9") (pintype "power_in"))
      (node (ref "IC5") (pin "1") (pinfunction "CPVDD_1") (pintype "bidirectional"))
      (node (ref "IC5") (pin "8") (pinfunction "AVDD_8") (pintype "power_in"))
      (node (ref "IC6") (pin "4") (pinfunction "V+_4") (pintype "power_in"))
      (node (ref "IC7") (pin "4") (pinfunction "V+_4") (pintype "power_in"))
      (node (ref "R1") (pin "P$1") (pinfunction "E_P$1") (pintype "passive"))
      (node (ref "R2") (pin "P$1") (pinfunction "E_P$1") (pintype "passive"))
      (node (ref "R42") (pin "P$1") (pinfunction "E_P$1") (pintype "passive"))
      (node (ref "R43") (pin "P$1") (pinfunction "E_P$1") (pintype "passive"))
      (node (ref "R44") (pin "P$1") (pinfunction "E_P$1") (pintype "passive"))
      (node (ref "R7") (pin "P$1") (pinfunction "E_P$1") (pintype "passive"))
      (node (ref "R8") (pin "P$1") (pinfunction "E_P$1") (pintype "passive"))
    )
    (net (code "3") (name "ADC_FM") (class "Default")
      (node (ref "C40") (pin "2") (pinfunction "2_2") (pintype "passive"))
      (node (ref "IC4") (pin "22") (pinfunction "PE9/SDADC1_AIN7P/SDADC1_AIN8M/SDADC2_AIN7P/SDADC2_AIN8M_22") (pintype "bidirectional"))
      (node (ref "IC7") (pin "1") (pinfunction "OUT_1") (pintype "output"))
      (node (ref "R19") (pin "1") (pinfunction "1_1") (pintype "passive"))
    )
    (net (code "4") (name "ADC_GATE") (class "Default")
      (node (ref "C39") (pin "2") (pinfunction "2_2") (pintype "passive"))
      (node (ref "IC4") (pin "21") (pinfunction "PE8/SDADC1_AIN8P/SDADC2_AIN8P_21") (pintype "bidirectional"))
      (node (ref "IC6") (pin "14") (pinfunction "OUT_14") (pintype "output"))
      (node (ref "R18") (pin "1") (pinfunction "1_1") (pintype "passive"))
    )
    (net (code "5") (name "ADC_HARMONICS") (class "Default")
      (node (ref "C41") (pin "2") (pinfunction "2_2") (pintype "passive"))
      (node (ref "IC4") (pin "28") (pinfunction "PD8/SPI2_SCK/I2S2_CK/USART3_TX/SDADC3_AIN6P_28") (pintype "bidirectional"))
      (node (ref "IC7") (pin "14") (pinfunction "OUT_14") (pintype "output"))
      (node (ref "R20") (pin "1") (pinfunction "1_1") (pintype "passive"))
    )
    (net (code "6") (name "ADC_MODEL") (class "Default")
      (node (ref "C46") (pin "2") (pinfunction "2_2") (pintype "passive"))
      (node (ref "IC4") (pin "19") (pinfunction "PB1/TIM3_CH4/ADC_IN9/SDADC1_AIN5P/SDADC1_AIN6M_19") (pintype "bidirectional"))
      (node (ref "IC6") (pin "7") (pinfunction "OUT_7") (pintype "output"))
      (node (ref "R31") (pin "1") (pinfunction "1_1") (pintype "passive"))
    )
    (net (code "7") (name "ADC_MORPH") (class "Default")
      (node (ref "C49") (pin "2") (pinfunction "2_2") (pintype "passive"))
      (node (ref "IC4") (pin "27") (pinfunction "PB15/SPI2_MOSI/I2S2_SD/SDADC3_AIN7P/SDADC3_AIN8M_27") (pintype "bidirectional"))
      (node (ref "IC7") (pin "8") (pinfunction "OUT_8") (pintype "output"))
      (node (ref "R35") (pin "1") (pinfunction "1_1") (pintype "passive"))
    )
    (net (code "8") (name "ADC_TIMBRE") (class "Default")
      (node (ref "C47") (pin "2") (pinfunction "2_2") (pintype "passive"))
      (node (ref "IC4") (pin "20") (pinfunction "PB2/SDADC1_AIN4P/SDADC2_AIN6P_20") (pintype "bidirectional"))
      (node (ref "IC6") (pin "8") (pinfunction "OUT_8") (pintype "output"))
      (node (ref "R32") (pin "1") (pinfunction "1_1") (pintype "passive"))
    )
    (net (code "9") (name "ADC_TRIG") (class "Default")
      (node (ref "C38") (pin "2") (pinfunction "2_2") (pintype "passive"))
      (node (ref "IC4") (pin "18") (pinfunction "PB0/SPI1_MOSI/I2S1_SD/TIM3_CH3/ADC_IN8/SDADC1_AIN6P_18") (pintype "bidirectional"))
      (node (ref "IC6") (pin "1") (pinfunction "OUT_1") (pintype "output"))
      (node (ref "R17") (pin "1") (pinfunction "1_1") (pintype "passive"))
    )
    (net (code "10") (name "ADC_V_OCT") (class "Default")
      (node (ref "C48") (pin "2") (pinfunction "2_2") (pintype "passive"))
      (node (ref "IC4") (pin "26") (pinfunction "PB14/SPI2_MISO/I2S2_MCK/USART3_RTS/SDADC3_AIN8P_26") (pintype "bidirectional"))
      (node (ref "IC7") (pin "7") (pinfunction "OUT_7") (pintype "output"))
      (node (ref "R34") (pin "1") (pinfunction "1_1") (pintype "passive"))
    )
    (net (code "11") (name "AREF_-10") (class "Default")
      (node (ref "C50") (pin "1") (pinfunction "1_1") (pintype "passive"))
      (node (ref "IC9") (pin "2") (pinfunction "A_2") (pintype "passive"))
      (node (ref "R23") (pin "2") (pinfunction "2_2") (pintype "passive"))
      (node (ref "R25") (pin "2") (pinfunction "2_2") (pintype "passive"))
      (node (ref "R26") (pin "2") (pinfunction "2_2") (pintype "passive"))
      (node (ref "R27") (pin "2") (pinfunction "2_2") (pintype "passive"))
      (node (ref "R29") (pin "2") (pinfunction "2_2") (pintype "passive"))
      (node (ref "R30") (pin "2") (pinfunction "2_2") (pintype "passive"))
      (node (ref "R33") (pin "2") (pinfunction "2_2") (pintype "passive"))
      (node (ref "R36") (pin "2") (pinfunction "2_2") (pintype "passive"))
      (node (ref "R37") (pin "2") (pinfunction "2_2") (pintype "passive"))
    )
    (net (code "12") (name "DAC_BCK") (class "Default")
      (node (ref "IC4") (pin "29") (pinfunction "PA8/SPI2_SCK/I2S2_CK/I2C2_SMBA/USART1_CK/TIM5_CH1_29") (pintype "bidirectional"))
      (node (ref "IC5") (pin "13") (pinfunction "BCK_13") (pintype "input"))
    )
    (net (code "13") (name "DAC_DIN") (class "Default")
      (node (ref "IC4") (pin "31") (pinfunction "PA10/SPI2_MOSI/I2S2_SD/I2C2_SDA/USART1_RX/TIM2_CH4_31") (pintype "bidirectional"))
      (node (ref "IC5") (pin "14") (pinfunction "DIN_14") (pintype "input"))
    )
    (net (code "14") (name "DAC_LRCK") (class "Default")
      (node (ref "IC4") (pin "32") (pinfunction "PA11/SPI2_NSS/I2S2_WS/SPI1_NSS/I2S1_WS/USART1_CTS/CAN_RX/TIM4_CH1/TIM5_CH2_32") (pintype "bidirectional"))
      (node (ref "IC5") (pin "15") (pinfunction "LRCK_15") (pintype "input"))
    )
    (net (code "15") (name "FREQ_ATT") (class "Default")
      (node (ref "C51") (pin "1") (pinfunction "1_1") (pintype "passive"))
      (node (ref "IC4") (pin "15") (pinfunction "PA5/SPI1_SCK/I2S1_CK/TIM2_CH1/ADC_IN5/DAC1_OUT2_15") (pintype "bidirectional"))
      (node (ref "R43") (pin "P$2") (pinfunction "S_P$2") (pintype "passive"))
    )
    (net (code "16") (name "FREQ_POT") (class "Default")
      (node (ref "C11") (pin "1") (pinfunction "1_1") (pintype "passive"))
      (node (ref "IC4") (pin "10") (pinfunction "PA0/USART2_CTS/TIM2_CH1/TIM5_CH1/ADC_IN0_10") (pintype "bidirectional"))
      (node (ref "R1") (pin "P$2") (pinfunction "S_P$2") (pintype "passive"))
    )
    (net (code "17") (name "GND") (class "Default")
      (node (ref "C1") (pin "2") (pinfunction "2_2") (pintype "passive"))
      (node (ref "C10") (pin "2") (pinfunction "2_2") (pintype "passive"))
      (node (ref "C11") (pin "2") (pinfunction "2_2") (pintype "passive"))
      (node (ref "C12") (pin "2") (pinfunction "2_2") (pintype "passive"))
      (node (ref "C13") (pin "2") (pinfunction "2_2") (pintype "passive"))
      (node (ref "C14") (pin "1") (pinfunction "1_1") (pintype "passive"))
      (node (ref "C15") (pin "2") (pinfunction "2_2") (pintype "passive"))
      (node (ref "C16") (pin "-") (pinfunction "-_-") (pintype "passive"))
      (node (ref "C17") (pin "2") (pinfunction "2_2") (pintype "passive"))
      (node (ref "C18") (pin "2") (pinfunction "2_2") (pintype "passive"))
      (node (ref "C19") (pin "2") (pinfunction "2_2") (pintype "passive"))
      (node (ref "C2") (pin "2") (pinfunction "2_2") (pintype "passive"))
      (node (ref "C20") (pin "2") (pinfunction "2_2") (pintype "passive"))
      (node (ref "C21") (pin "1") (pinfunction "1_1") (pintype "passive"))
      (node (ref "C22") (pin "-") (pinfunction "-_-") (pintype "passive"))
      (node (ref "C23") (pin "2") (pinfunction "2_2") (pintype "passive"))
      (node (ref "C24") (pin "2") (pinfunction "2_2") (pintype "passive"))
      (node (ref "C25") (pin "2") (pinfunction "2_2") (pintype "passive"))
      (node (ref "C26") (pin "2") (pinfunction "2_2") (pintype "passive"))
      (node (ref "C27") (pin "2") (pinfunction "2_2") (pintype "passive"))
      (node (ref "C28") (pin "2") (pinfunction "2_2") (pintype "passive"))
      (node (ref "C3") (pin "-") (pinfunction "-_-") (pintype "passive"))
      (node (ref "C30") (pin "-") (pinfunction "-_-") (pintype "passive"))
      (node (ref "C31") (pin "2") (pinfunction "2_2") (pintype "passive"))
      (node (ref "C32") (pin "2") (pinfunction "2_2") (pintype "passive"))
      (node (ref "C33") (pin "2") (pinfunction "2_2") (pintype "passive"))
      (node (ref "C34") (pin "2") (pinfunction "2_2") (pintype "passive"))
      (node (ref "C35") (pin "2") (pinfunction "2_2") (pintype "passive"))
      (node (ref "C36") (pin "2") (pinfunction "2_2") (pintype "passive"))
      (node (ref "C37") (pin "2") (pinfunction "2_2") (pintype "passive"))
      (node (ref "C4") (pin "-") (pinfunction "-_-") (pintype "passive"))
      (node (ref "C44") (pin "2") (pinfunction "2_2") (pintype "passive"))
      (node (ref "C45") (pin "1") (pinfunction "1_1") (pintype "passive"))
      (node (ref "C5") (pin "+") (pinfunction "+_+") (pintype "passive"))
      (node (ref "C50") (pin "2") (pinfunction "2_2") (pintype "passive"))
      (node (ref "C51") (pin "2") (pinfunction "2_2") (pintype "passive"))
      (node (ref "C52") (pin "2") (pinfunction "2_2") (pintype "passive"))
      (node (ref "C53") (pin "2") (pinfunction "2_2") (pintype "passive"))
      (node (ref "C54") (pin "2") (pinfunction "2_2") (pintype "passive"))
      (node (ref "C55") (pin "2") (pinfunction "2_2") (pintype "passive"))
      (node (ref "C56") (pin "2") (pinfunction "2_2") (pintype "passive"))
      (node (ref "C57") (pin "2") (pinfunction "2_2") (pintype "passive"))
      (node (ref "C58") (pin "2") (pinfunction "2_2") (pintype "passive"))
      (node (ref "C59") (pin "2") (pinfunction "2_2") (pintype "passive"))
      (node (ref "C6") (pin "2") (pinfunction "2_2") (pintype "passive"))
      (node (ref "C60") (pin "2") (pinfunction "2_2") (pintype "passive"))
      (node (ref "C61") (pin "2") (pinfunction "2_2") (pintype "passive"))
      (node (ref "C7") (pin "-") (pinfunction "-_-") (pintype "passive"))
      (node (ref "C8") (pin "2") (pinfunction "2_2") (pintype "passive"))
      (node (ref "C9") (pin "2") (pinfunction "2_2") (pintype "passive"))
      (node (ref "D3") (pin "1") (pinfunction "A_1") (pintype "passive"))
      (node (ref "IC1") (pin "2") (pinfunction "GND_2") (pintype "passive"))
      (node (ref "IC2") (pin "1") (pinfunction "GND_1") (pintype "bidirectional"))
      (node (ref "IC2") (pin "21") (pinfunction "BLANK_21") (pintype "bidirectional"))
      (node (ref "IC3") (pin "2") (pinfunction "GND_2") (pintype "passive"))
      (node (ref "IC4") (pin "23") (pinfunction "VSSSD/VREFSD-_23") (pintype "power_in"))
      (node (ref "IC4") (pin "44") (pinfunction "BOOT0_44") (pintype "bidirectional"))
      (node (ref "IC4") (pin "47") (pinfunction "VSS_1_47") (pintype "power_in"))
      (node (ref "IC4") (pin "8") (pinfunction "VSSA_8") (pintype "power_in"))
      (node (ref "IC5") (pin "10") (pinfunction "DEMP_10") (pintype "input"))
      (node (ref "IC5") (pin "12") (pinfunction "SCK_12") (pintype "input"))
      (node (ref "IC5") (pin "16") (pinfunction "FMT_16") (pintype "input"))
      (node (ref "IC5") (pin "19") (pinfunction "DGND_19") (pintype "power_in"))
      (node (ref "IC5") (pin "3") (pinfunction "CPGND_3") (pintype "bidirectional"))
      (node (ref "IC5") (pin "9") (pinfunction "AGND_9") (pintype "power_in"))
      (node (ref "IC6") (pin "10") (pinfunction "+IN_10") (pintype "input"))
      (node (ref "IC6") (pin "11") (pinfunction "V-_11") (pintype "power_in"))
      (node (ref "IC6") (pin "12") (pinfunction "+IN_12") (pintype "input"))
      (node (ref "IC6") (pin "3") (pinfunction "+IN_3") (pintype "input"))
      (node (ref "IC6") (pin "5") (pinfunction "+IN_5") (pintype "input"))
      (node (ref "IC7") (pin "10") (pinfunction "+IN_10") (pintype "input"))
      (node (ref "IC7") (pin "11") (pinfunction "V-_11") (pintype "power_in"))
      (node (ref "IC7") (pin "12") (pinfunction "+IN_12") (pintype "input"))
      (node (ref "IC7") (pin "3") (pinfunction "+IN_3") (pintype "input"))
      (node (ref "IC7") (pin "5") (pinfunction "+IN_5") (pintype "input"))
      (node (ref "IC8") (pin "3") (pinfunction "+IN_3") (pintype "input"))
      (node (ref "IC8") (pin "5") (pinfunction "+IN_5") (pintype "input"))
      (node (ref "IC9") (pin "1") (pinfunction "C_1") (pintype "passive"))
      (node (ref "J1") (pin "P1") (pinfunction "1_P1") (pintype "passive"))
      (node (ref "J1") (pin "P2") (pinfunction "2_P2") (pintype "passive"))
      (node (ref "J10") (pin "P1") (pinfunction "1_P1") (pintype "passive"))
      (node (ref "J2") (pin "P1") (pinfunction "1_P1") (pintype "passive"))
      (node (ref "J3") (pin "P1") (pinfunction "1_P1") (pintype "passive"))
      (node (ref "J4") (pin "P1") (pinfunction "1_P1") (pintype "passive"))
      (node (ref "J5") (pin "P1") (pinfunction "1_P1") (pintype "passive"))
      (node (ref "J5") (pin "P2") (pinfunction "2_P2") (pintype "passive"))
      (node (ref "J6") (pin "P1") (pinfunction "1_P1") (pintype "passive"))
      (node (ref "J7") (pin "P1") (pinfunction "1_P1") (pintype "passive"))
      (node (ref "J8") (pin "P1") (pinfunction "1_P1") (pintype "passive"))
      (node (ref "J8") (pin "P2") (pinfunction "2_P2") (pintype "passive"))
      (node (ref "J9") (pin "P1") (pinfunction "1_P1") (pintype "passive"))
      (node (ref "JP6") (pin "1") (pinfunction "1_1") (pintype "passive"))
      (node (ref "JP8") (pin "3") (pinfunction "3_3") (pintype "passive"))
      (node (ref "JP8") (pin "4") (pinfunction "4_4") (pintype "passive"))
      (node (ref "JP8") (pin "5") (pinfunction "5_5") (pintype "passive"))
      (node (ref "JP8") (pin "6") (pinfunction "6_6") (pintype "passive"))
      (node (ref "JP8") (pin "7") (pinfunction "7_7") (pintype "passive"))
      (node (ref "JP8") (pin "8") (pinfunction "8_8") (pintype "passive"))
      (node (ref "Q1") (pin "2") (pinfunction "LID1_2") (pintype "power_in"))
      (node (ref "Q1") (pin "4") (pinfunction "LID2_4") (pintype "power_in"))
      (node (ref "R1") (pin "P$3") (pinfunction "A_P$3") (pintype "passive"))
      (node (ref "R2") (pin "P$3") (pinfunction "A_P$3") (pintype "passive"))
      (node (ref "R3") (pin "2") (pinfunction "2_2") (pintype "passive"))
      (node (ref "R42") (pin "P$3") (pinfunction "A_P$3") (pintype "passive"))
      (node (ref "R43") (pin "P$3") (pinfunction "A_P$3") (pintype "passive"))
      (node (ref "R44") (pin "P$3") (pinfunction "A_P$3") (pintype "passive"))
      (node (ref "R7") (pin "P$3") (pinfunction "A_P$3") (pintype "passive"))
      (node (ref "R8") (pin "P$3") (pinfunction "A_P$3") (pintype "passive"))
      (node (ref "SW1") (pin "1") (pinfunction "1_1") (pintype "passive"))
      (node (ref "SW1") (pin "2") (pinfunction "2_2") (pintype "passive"))
      (node (ref "SW2") (pin "1") (pinfunction "1_1") (pintype "passive"))
      (node (ref "SW2") (pin "2") (pinfunction "2_2") (pintype "passive"))
    )
    (net (code "18") (name "HARMONICS_POT") (class "Default")
      (node (ref "C12") (pin "1") (pinfunction "1_1") (pintype "passive"))
      (node (ref "IC4") (pin "12") (pinfunction "PA2/SPI3_MISO/I2S3_MCK/USART2_TX/TIM2_CH3/TIM5_CH3/ADC_IN2_12") (pintype "bidirectional"))
      (node (ref "R2") (pin "P$2") (pinfunction "S_P$2") (pintype "passive"))
    )
    (net (code "19") (name "LEDS_SCK") (class "Default")
      (node (ref "IC2") (pin "3") (pinfunction "SCLK_3") (pintype "bidirectional"))
      (node (ref "IC4") (pin "33") (pinfunction "PA12/SPI1_SCK/I2S1_CK/USART1_RTS/CAN_TX/TIM4_CH2/TIM5_CH3_33") (pintype "bidirectional"))
    )
    (net (code "20") (name "LEDS_SIN") (class "Default")
      (node (ref "IC2") (pin "2") (pinfunction "SIN_2") (pintype "bidirectional"))
      (node (ref "IC4") (pin "35") (pinfunction "PF6/SPI1_MOSI/I2S1_SD/USART3_RTS/TIM4_CH4/I2C2_SCL_35") (pintype "bidirectional"))
    )
    (net (code "21") (name "LEDS_SS") (class "Default")
      (node (ref "IC2") (pin "4") (pinfunction "LAT_4") (pintype "bidirectional"))
      (node (ref "IC4") (pin "36") (pinfunction "PF7/I2C2_SDA/USART2_CK_36") (pintype "bidirectional"))
    )
    (net (code "22") (name "MORPH_ATT") (class "Default")
      (node (ref "C52") (pin "1") (pinfunction "1_1") (pintype "passive"))
      (node (ref "IC4") (pin "14") (pinfunction "PA4/SPI1_NSS/I2S1_WS/SPI3_NSS/I2S3_WS/USART2_CK/TIM3_CH2/ADC_IN4/DAC1_OUT1_14") (pintype "bidirectional"))
      (node (ref "R44") (pin "P$2") (pinfunction "S_P$2") (pintype "passive"))
    )
    (net (code "23") (name "MORPH_POT") (class "Default")
      (node (ref "C34") (pin "1") (pinfunction "1_1") (pintype "passive"))
      (node (ref "IC4") (pin "11") (pinfunction "PA1/SPI3_SCK/I2S3_CK/USART2_RTS/TIM2_CH2/TIM5_CH2/ADC_IN1_11") (pintype "bidirectional"))
      (node (ref "R8") (pin "P$2") (pinfunction "S_P$2") (pintype "passive"))
    )
    (net (code "24") (name "NORMALIZATION_PROBE") (class "Default")
      (node (ref "D3") (pin "3") (pinfunction "AC_3") (pintype "passive"))
      (node (ref "IC4") (pin "30") (pinfunction "PA9/SPI_MISO/I2S2_MCK/I2C2_SCL/USART1_TX/TIM2_CH3_30") (pintype "bidirectional"))
      (node (ref "R45") (pin "2") (pinfunction "2_2") (pintype "passive"))
      (node (ref "R48") (pin "2") (pinfunction "2_2") (pintype "passive"))
      (node (ref "R49") (pin "2") (pinfunction "2_2") (pintype "passive"))
      (node (ref "R50") (pin "1") (pinfunction "1_1") (pintype "passive"))
      (node (ref "R51") (pin "2") (pinfunction "2_2") (pintype "passive"))
    )
    (net (code "25") (name "Net-(C2-Pad1)") (class "Default")
      (node (ref "C2") (pin "1") (pinfunction "1_1") (pintype "passive"))
      (node (ref "D1") (pin "C") (pinfunction "C_C") (pintype "passive"))
      (node (ref "L1") (pin "1") (pinfunction "1_1") (pintype "passive"))
      (node (ref "L2") (pin "2") (pinfunction "2_2") (pintype "passive"))
      (node (ref "L5") (pin "2") (pinfunction "2_2") (pintype "passive"))
    )
    (net (code "26") (name "Net-(C21-Pad2)") (class "Default")
      (node (ref "C21") (pin "2") (pinfunction "2_2") (pintype "passive"))
      (node (ref "Q1") (pin "1") (pinfunction "1_1") (pintype "passive"))
      (node (ref "R6") (pin "2") (pinfunction "2_2") (pintype "passive"))
    )
    (net (code "27") (name "Net-(C33-Pad1)") (class "Default")
      (node (ref "C33") (pin "1") (pinfunction "1_1") (pintype "passive"))
      (node (ref "R11") (pin "1") (pinfunction "1_1") (pintype "passive"))
      (node (ref "R21") (pin "2") (pinfunction "2_2") (pintype "passive"))
    )
    (net (code "28") (name "Net-(C35-Pad1)") (class "Default")
      (node (ref "C35") (pin "1") (pinfunction "1_1") (pintype "passive"))
      (node (ref "R12") (pin "1") (pinfunction "1_1") (pintype "passive"))
      (node (ref "R16") (pin "2") (pinfunction "2_2") (pintype "passive"))
    )
    (net (code "29") (name "Net-(D1-PadA)") (class "Default")
      (node (ref "D1") (pin "A") (pinfunction "A_A") (pintype "passive"))
      (node (ref "JP8") (pin "10") (pinfunction "10_10") (pintype "passive"))
      (node (ref "JP8") (pin "9") (pinfunction "9_9") (pintype "passive"))
    )
    (net (code "30") (name "Net-(D2-PadA)") (class "Default")
      (node (ref "D2") (pin "A") (pinfunction "A_A") (pintype "passive"))
      (node (ref "L3") (pin "2") (pinfunction "2_2") (pintype "passive"))
    )
    (net (code "31") (name "Net-(D2-PadC)") (class "Default")
      (node (ref "D2") (pin "C") (pinfunction "C_C") (pintype "passive"))
      (node (ref "JP8") (pin "1") (pinfunction "1_1") (pintype "passive"))
      (node (ref "JP8") (pin "2") (pinfunction "2_2") (pintype "passive"))
    )
    (net (code "32") (name "Net-(IC1-VI)") (class "Default")
      (node (ref "C1") (pin "1") (pinfunction "1_1") (pintype "passive"))
      (node (ref "IC1") (pin "1") (pinfunction "VI_1") (pintype "input"))
      (node (ref "L1") (pin "2") (pinfunction "2_2") (pintype "passive"))
    )
    (net (code "33") (name "Net-(IC2-IREF)") (class "Default")
      (node (ref "IC2") (pin "23") (pinfunction "IREF_23") (pintype "bidirectional"))
      (node (ref "R3") (pin "1") (pinfunction "1_1") (pintype "passive"))
    )
    (net (code "34") (name "Net-(IC2-OUT0)") (class "Default")
      (node (ref "IC2") (pin "5") (pinfunction "OUT0_5") (pintype "bidirectional"))
      (node (ref "LED5") (pin "RED_C") (pinfunction "RED_RED_C") (pintype "bidirectional"))
    )
    (net (code "35") (name "Net-(IC2-OUT1)") (class "Default")
      (node (ref "IC2") (pin "6") (pinfunction "OUT1_6") (pintype "bidirectional"))
      (node (ref "LED5") (pin "GREEN_C") (pinfunction "GRN_GREEN_C") (pintype "bidirectional"))
    )
    (net (code "36") (name "Net-(IC2-OUT2)") (class "Default")
      (node (ref "IC2") (pin "7") (pinfunction "OUT2_7") (pintype "bidirectional"))
      (node (ref "LED6") (pin "RED_C") (pinfunction "RED_RED_C") (pintype "bidirectional"))
    )
    (net (code "37") (name "Net-(IC2-OUT3)") (class "Default")
      (node (ref "IC2") (pin "8") (pinfunction "OUT3_8") (pintype "bidirectional"))
      (node (ref "LED6") (pin "GREEN_C") (pinfunction "GRN_GREEN_C") (pintype "bidirectional"))
    )
    (net (code "38") (name "Net-(IC2-OUT4)") (class "Default")
      (node (ref "IC2") (pin "9") (pinfunction "OUT4_9") (pintype "bidirectional"))
      (node (ref "LED7") (pin "RED_C") (pinfunction "RED_RED_C") (pintype "bidirectional"))
    )
    (net (code "39") (name "Net-(IC2-OUT5)") (class "Default")
      (node (ref "IC2") (pin "10") (pinfunction "OUT5_10") (pintype "bidirectional"))
      (node (ref "LED7") (pin "GREEN_C") (pinfunction "GRN_GREEN_C") (pintype "bidirectional"))
    )
    (net (code "40") (name "Net-(IC2-OUT6)") (class "Default")
      (node (ref "IC2") (pin "11") (pinfunction "OUT6_11") (pintype "bidirectional"))
      (node (ref "LED8") (pin "RED_C") (pinfunction "RED_RED_C") (pintype "bidirectional"))
    )
    (net (code "41") (name "Net-(IC2-OUT7)") (class "Default")
      (node (ref "IC2") (pin "12") (pinfunction "OUT7_12") (pintype "bidirectional"))
      (node (ref "LED8") (pin "GREEN_C") (pinfunction "GRN_GREEN_C") (pintype "bidirectional"))
    )
    (net (code "42") (name "Net-(IC2-OUT8)") (class "Default")
      (node (ref "IC2") (pin "13") (pinfunction "OUT8_13") (pintype "bidirectional"))
      (node (ref "LED4") (pin "RED_C") (pinfunction "RED_RED_C") (pintype "bidirectional"))
    )
    (net (code "43") (name "Net-(IC2-OUT9)") (class "Default")
      (node (ref "IC2") (pin "14") (pinfunction "OUT9_14") (pintype "bidirectional"))
      (node (ref "LED4") (pin "GREEN_C") (pinfunction "GRN_GREEN_C") (pintype "bidirectional"))
    )
    (net (code "44") (name "Net-(IC2-OUT10)") (class "Default")
      (node (ref "IC2") (pin "15") (pinfunction "OUT10_15") (pintype "bidirectional"))
      (node (ref "LED3") (pin "RED_C") (pinfunction "RED_RED_C") (pintype "bidirectional"))
    )
    (net (code "45") (name "Net-(IC2-OUT11)") (class "Default")
      (node (ref "IC2") (pin "16") (pinfunction "OUT11_16") (pintype "bidirectional"))
      (node (ref "LED3") (pin "GREEN_C") (pinfunction "GRN_GREEN_C") (pintype "bidirectional"))
    )
    (net (code "46") (name "Net-(IC2-OUT12)") (class "Default")
      (node (ref "IC2") (pin "17") (pinfunction "OUT12_17") (pintype "bidirectional"))
      (node (ref "LED2") (pin "RED_C") (pinfunction "RED_RED_C") (pintype "bidirectional"))
    )
    (net (code "47") (name "Net-(IC2-OUT13)") (class "Default")
      (node (ref "IC2") (pin "18") (pinfunction "OUT13_18") (pintype "bidirectional"))
      (node (ref "LED2") (pin "GREEN_C") (pinfunction "GRN_GREEN_C") (pintype "bidirectional"))
    )
    (net (code "48") (name "Net-(IC2-OUT14)") (class "Default")
      (node (ref "IC2") (pin "19") (pinfunction "OUT14_19") (pintype "bidirectional"))
      (node (ref "LED1") (pin "RED_C") (pinfunction "RED_RED_C") (pintype "bidirectional"))
    )
    (net (code "49") (name "Net-(IC2-OUT15)") (class "Default")
      (node (ref "IC2") (pin "20") (pinfunction "OUT15_20") (pintype "bidirectional"))
      (node (ref "LED1") (pin "GREEN_C") (pinfunction "GRN_GREEN_C") (pintype "bidirectional"))
    )
    (net (code "50") (name "Net-(IC2-VCC)") (class "Default")
      (node (ref "C7") (pin "+") (pinfunction "+_+") (pintype "passive"))
      (node (ref "C8") (pin "1") (pinfunction "1_1") (pintype "passive"))
      (node (ref "IC2") (pin "24") (pinfunction "VCC_24") (pintype "bidirectional"))
      (node (ref "L4") (pin "1") (pinfunction "1_1") (pintype "passive"))
    )
    (net (code "51") (name "Net-(IC3-VI)") (class "Default")
      (node (ref "C13") (pin "1") (pinfunction "1_1") (pintype "passive"))
      (node (ref "IC3") (pin "3") (pinfunction "VI_3") (pintype "input"))
      (node (ref "L5") (pin "1") (pinfunction "1_1") (pintype "passive"))
    )
    (net (code "52") (name "Net-(IC4-PF0{slash}OSC_IN{slash}I2C2_SDA)") (class "Default")
      (node (ref "IC4") (pin "5") (pinfunction "PF0/OSC_IN/I2C2_SDA_5") (pintype "bidirectional"))
      (node (ref "R5") (pin "1") (pinfunction "1_1") (pintype "passive"))
    )
    (net (code "53") (name "Net-(IC4-PF1{slash}OSC_OUT{slash}I2C2_SCL)") (class "Default")
      (node (ref "IC4") (pin "6") (pinfunction "PF1/OSC_OUT/I2C2_SCL_6") (pintype "bidirectional"))
      (node (ref "R6") (pin "1") (pinfunction "1_1") (pintype "passive"))
    )
    (net (code "54") (name "Net-(IC5-CAPM)") (class "Default")
      (node (ref "C29") (pin "2") (pinfunction "2_2") (pintype "passive"))
      (node (ref "IC5") (pin "4") (pinfunction "CAPM_4") (pintype "bidirectional"))
    )
    (net (code "55") (name "Net-(IC5-CAPP)") (class "Default")
      (node (ref "C29") (pin "1") (pinfunction "1_1") (pintype "passive"))
      (node (ref "IC5") (pin "2") (pinfunction "CAPP_2") (pintype "bidirectional"))
    )
    (net (code "56") (name "Net-(IC5-LDOO)") (class "Default")
      (node (ref "C18") (pin "1") (pinfunction "1_1") (pintype "passive"))
      (node (ref "IC5") (pin "18") (pinfunction "LDOO_18") (pintype "bidirectional"))
    )
    (net (code "57") (name "Net-(IC5-OUTL)") (class "Default")
      (node (ref "IC5") (pin "6") (pinfunction "OUTL_6") (pintype "output"))
      (node (ref "R11") (pin "2") (pinfunction "2_2") (pintype "passive"))
    )
    (net (code "58") (name "Net-(IC5-OUTR)") (class "Default")
      (node (ref "IC5") (pin "7") (pinfunction "OUTR_7") (pintype "output"))
      (node (ref "R12") (pin "2") (pinfunction "2_2") (pintype "passive"))
    )
    (net (code "59") (name "Net-(IC5-VNEG)") (class "Default")
      (node (ref "C31") (pin "1") (pinfunction "1_1") (pintype "passive"))
      (node (ref "IC5") (pin "5") (pinfunction "VNEG_5") (pintype "input"))
    )
    (net (code "60") (name "Net-(IC6A--IN)") (class "Default")
      (node (ref "C38") (pin "1") (pinfunction "1_1") (pintype "passive"))
      (node (ref "IC6") (pin "2") (pinfunction "-IN_2") (pintype "input"))
      (node (ref "R17") (pin "2") (pinfunction "2_2") (pintype "passive"))
      (node (ref "R24") (pin "1") (pinfunction "1_1") (pintype "passive"))
      (node (ref "R25") (pin "1") (pinfunction "1_1") (pintype "passive"))
    )
    (net (code "61") (name "Net-(IC6B--IN)") (class "Default")
      (node (ref "C46") (pin "1") (pinfunction "1_1") (pintype "passive"))
      (node (ref "IC6") (pin "6") (pinfunction "-IN_6") (pintype "input"))
      (node (ref "R30") (pin "1") (pinfunction "1_1") (pintype "passive"))
      (node (ref "R31") (pin "2") (pinfunction "2_2") (pintype "passive"))
      (node (ref "R40") (pin "1") (pinfunction "1_1") (pintype "passive"))
    )
    (net (code "62") (name "Net-(IC6C--IN)") (class "Default")
      (node (ref "C47") (pin "1") (pinfunction "1_1") (pintype "passive"))
      (node (ref "IC6") (pin "9") (pinfunction "-IN_9") (pintype "input"))
      (node (ref "R32") (pin "2") (pinfunction "2_2") (pintype "passive"))
      (node (ref "R33") (pin "1") (pinfunction "1_1") (pintype "passive"))
      (node (ref "R41") (pin "1") (pinfunction "1_1") (pintype "passive"))
    )
    (net (code "63") (name "Net-(IC6D--IN)") (class "Default")
      (node (ref "C39") (pin "1") (pinfunction "1_1") (pintype "passive"))
      (node (ref "IC6") (pin "13") (pinfunction "-IN_13") (pintype "input"))
      (node (ref "R14") (pin "1") (pinfunction "1_1") (pintype "passive"))
      (node (ref "R18") (pin "2") (pinfunction "2_2") (pintype "passive"))
      (node (ref "R26") (pin "1") (pinfunction "1_1") (pintype "passive"))
    )
    (net (code "64") (name "Net-(IC7A--IN)") (class "Default")
      (node (ref "C40") (pin "1") (pinfunction "1_1") (pintype "passive"))
      (node (ref "IC7") (pin "2") (pinfunction "-IN_2") (pintype "input"))
      (node (ref "R15") (pin "1") (pinfunction "1_1") (pintype "passive"))
      (node (ref "R19") (pin "2") (pinfunction "2_2") (pintype "passive"))
      (node (ref "R23") (pin "1") (pinfunction "1_1") (pintype "passive"))
    )
    (net (code "65") (name "Net-(IC7B--IN)") (class "Default")
      (node (ref "C48") (pin "1") (pinfunction "1_1") (pintype "passive"))
      (node (ref "IC7") (pin "6") (pinfunction "-IN_6") (pintype "input"))
      (node (ref "R29") (pin "1") (pinfunction "1_1") (pintype "passive"))
      (node (ref "R34") (pin "2") (pinfunction "2_2") (pintype "passive"))
      (node (ref "R38") (pin "1") (pinfunction "1_1") (pintype "passive"))
    )
    (net (code "66") (name "Net-(IC7C--IN)") (class "Default")
      (node (ref "C49") (pin "1") (pinfunction "1_1") (pintype "passive"))
      (node (ref "IC7") (pin "9") (pinfunction "-IN_9") (pintype "input"))
      (node (ref "R35") (pin "2") (pinfunction "2_2") (pintype "passive"))
      (node (ref "R36") (pin "1") (pinfunction "1_1") (pintype "passive"))
      (node (ref "R39") (pin "1") (pinfunction "1_1") (pintype "passive"))
    )
    (net (code "67") (name "Net-(IC7D--IN)") (class "Default")
      (node (ref "C41") (pin "1") (pinfunction "1_1") (pintype "passive"))
      (node (ref "IC7") (pin "13") (pinfunction "-IN_13") (pintype "input"))
      (node (ref "R13") (pin "1") (pinfunction "1_1") (pintype "passive"))
      (node (ref "R20") (pin "2") (pinfunction "2_2") (pintype "passive"))
      (node (ref "R27") (pin "1") (pinfunction "1_1") (pintype "passive"))
    )
    (net (code "68") (name "Net-(IC8A--IN)") (class "Default")
      (node (ref "C42") (pin "1") (pinfunction "1_1") (pintype "passive"))
      (node (ref "IC8") (pin "2") (pinfunction "-IN_2") (pintype "input"))
      (node (ref "R21") (pin "1") (pinfunction "1_1") (pintype "passive"))
      (node (ref "R22") (pin "2") (pinfunction "2_2") (pintype "passive"))
    )
    (net (code "69") (name "Net-(IC8A-OUT)") (class "Default")
      (node (ref "C42") (pin "2") (pinfunction "2_2") (pintype "passive"))
      (node (ref "IC8") (pin "1") (pinfunction "OUT_1") (pintype "output"))
      (node (ref "R22") (pin "1") (pinfunction "1_1") (pintype "passive"))
      (node (ref "R46") (pin "2") (pinfunction "2_2") (pintype "passive"))
    )
    (net (code "70") (name "Net-(IC8B--IN)") (class "Default")
      (node (ref "C43") (pin "1") (pinfunction "1_1") (pintype "passive"))
      (node (ref "IC8") (pin "6") (pinfunction "-IN_6") (pintype "input"))
      (node (ref "R16") (pin "1") (pinfunction "1_1") (pintype "passive"))
      (node (ref "R28") (pin "2") (pinfunction "2_2") (pintype "passive"))
    )
    (net (code "71") (name "Net-(IC8B-OUT)") (class "Default")
      (node (ref "C43") (pin "2") (pinfunction "2_2") (pintype "passive"))
      (node (ref "IC8") (pin "7") (pinfunction "OUT_7") (pintype "output"))
      (node (ref "R28") (pin "1") (pinfunction "1_1") (pintype "passive"))
      (node (ref "R47") (pin "2") (pinfunction "2_2") (pintype "passive"))
    )
    (net (code "72") (name "Net-(J1-3)") (class "Default")
      (node (ref "C55") (pin "1") (pinfunction "1_1") (pintype "passive"))
      (node (ref "J1") (pin "P3") (pinfunction "3_P3") (pintype "passive"))
      (node (ref "R40") (pin "2") (pinfunction "2_2") (pintype "passive"))
    )
    (net (code "73") (name "Net-(J2-2)") (class "Default")
      (node (ref "J2") (pin "P2") (pinfunction "2_P2") (pintype "passive"))
      (node (ref "R48") (pin "1") (pinfunction "1_1") (pintype "passive"))
    )
    (net (code "74") (name "Net-(J2-3)") (class "Default")
      (node (ref "C56") (pin "1") (pinfunction "1_1") (pintype "passive"))
      (node (ref "J2") (pin "P3") (pinfunction "3_P3") (pintype "passive"))
      (node (ref "R41") (pin "2") (pinfunction "2_2") (pintype "passive"))
    )
    (net (code "75") (name "Net-(J3-2)") (class "Default")
      (node (ref "J3") (pin "P2") (pinfunction "2_P2") (pintype "passive"))
      (node (ref "R49") (pin "1") (pinfunction "1_1") (pintype "passive"))
    )
    (net (code "76") (name "Net-(J3-3)") (class "Default")
      (node (ref "C57") (pin "1") (pinfunction "1_1") (pintype "passive"))
      (node (ref "J3") (pin "P3") (pinfunction "3_P3") (pintype "passive"))
      (node (ref "R15") (pin "2") (pinfunction "2_2") (pintype "passive"))
    )
    (net (code "77") (name "Net-(J4-2)") (class "Default")
      (node (ref "J4") (pin "P2") (pinfunction "2_P2") (pintype "passive"))
      (node (ref "R45") (pin "1") (pinfunction "1_1") (pintype "passive"))
    )
    (net (code "78") (name "Net-(J4-3)") (class "Default")
      (node (ref "C54") (pin "1") (pinfunction "1_1") (pintype "passive"))
      (node (ref "J4") (pin "P3") (pinfunction "3_P3") (pintype "passive"))
      (node (ref "R39") (pin "2") (pinfunction "2_2") (pintype "passive"))
    )
    (net (code "79") (name "Net-(J5-3)") (class "Default")
      (node (ref "C58") (pin "1") (pinfunction "1_1") (pintype "passive"))
      (node (ref "J5") (pin "P3") (pinfunction "3_P3") (pintype "passive"))
      (node (ref "R13") (pin "2") (pinfunction "2_2") (pintype "passive"))
    )
    (net (code "80") (name "Net-(J6-2)") (class "Default")
      (node (ref "J6") (pin "P2") (pinfunction "2_P2") (pintype "passive"))
      (node (ref "R50") (pin "2") (pinfunction "2_2") (pintype "passive"))
    )
    (net (code "81") (name "Net-(J6-3)") (class "Default")
      (node (ref "C59") (pin "1") (pinfunction "1_1") (pintype "passive"))
      (node (ref "J6") (pin "P3") (pinfunction "3_P3") (pintype "passive"))
      (node (ref "R24") (pin "2") (pinfunction "2_2") (pintype "passive"))
    )
    (net (code "82") (name "Net-(J7-2)") (class "Default")
      (node (ref "J7") (pin "P2") (pinfunction "2_P2") (pintype "passive"))
      (node (ref "R51") (pin "1") (pinfunction "1_1") (pintype "passive"))
    )
    (net (code "83") (name "Net-(J7-3)") (class "Default")
      (node (ref "C61") (pin "1") (pinfunction "1_1") (pintype "passive"))
      (node (ref "J7") (pin "P3") (pinfunction "3_P3") (pintype "passive"))
      (node (ref "R14") (pin "2") (pinfunction "2_2") (pintype "passive"))
    )
    (net (code "84") (name "Net-(J8-3)") (class "Default")
      (node (ref "C60") (pin "1") (pinfunction "1_1") (pintype "passive"))
      (node (ref "J8") (pin "P3") (pinfunction "3_P3") (pintype "passive"))
      (node (ref "R38") (pin "2") (pinfunction "2_2") (pintype "passive"))
    )
    (net (code "85") (name "Net-(J9-3)") (class "Default")
      (node (ref "J9") (pin "P3") (pinfunction "3_P3") (pintype "passive"))
      (node (ref "R46") (pin "1") (pinfunction "1_1") (pintype "passive"))
    )
    (net (code "86") (name "Net-(J10-3)") (class "Default")
      (node (ref "J10") (pin "P3") (pinfunction "3_P3") (pintype "passive"))
      (node (ref "R47") (pin "1") (pinfunction "1_1") (pintype "passive"))
    )
    (net (code "87") (name "Net-(JP5-Pad1)") (class "Default")
      (node (ref "JP5") (pin "1") (pinfunction "1_1") (pintype "passive"))
      (node (ref "R9") (pin "1") (pinfunction "1_1") (pintype "passive"))
    )
    (net (code "88") (name "Net-(JP5-Pad2)") (class "Default")
      (node (ref "JP5") (pin "2") (pinfunction "2_2") (pintype "passive"))
      (node (ref "R10") (pin "1") (pinfunction "1_1") (pintype "passive"))
    )
    (net (code "89") (name "Net-(Q1B-2)") (class "Default")
      (node (ref "C14") (pin "2") (pinfunction "2_2") (pintype "passive"))
      (node (ref "Q1") (pin "3") (pinfunction "2_3") (pintype "passive"))
      (node (ref "R5") (pin "2") (pinfunction "2_2") (pintype "passive"))
    )
    (net (code "90") (name "RESET") (class "Default")
      (node (ref "C15") (pin "1") (pinfunction "1_1") (pintype "passive"))
      (node (ref "IC4") (pin "7") (pinfunction "NRST_7") (pintype "bidirectional"))
      (node (ref "JP6") (pin "4") (pinfunction "4_4") (pintype "passive"))
      (node (ref "R4") (pin "2") (pinfunction "2_2") (pintype "passive"))
    )
    (net (code "91") (name "RX") (class "Default")
      (node (ref "IC4") (pin "46") (pinfunction "PB9/SPI2_NSS/I2S2_WS/I2C1_SDA/USART3_RX/CAN_TX/TIM4_CH4_46") (pintype "bidirectional"))
      (node (ref "R9") (pin "2") (pinfunction "2_2") (pintype "passive"))
    )
    (net (code "92") (name "SWCLK") (class "Default")
      (node (ref "IC4") (pin "37") (pinfunction "PA14/I2C1_SDA/JTCK-SWCLK_37") (pintype "bidirectional"))
      (node (ref "JP6") (pin "3") (pinfunction "3_3") (pintype "passive"))
    )
    (net (code "93") (name "SWDIO") (class "Default")
      (node (ref "IC4") (pin "34") (pinfunction "PA13/SPI1_MISO/I2S1_MCK/USART3_CTS/TIM4_CH3/TIM5_CH4/JTMS-SWDIO_34") (pintype "bidirectional"))
      (node (ref "JP6") (pin "2") (pinfunction "2_2") (pintype "passive"))
    )
    (net (code "94") (name "SW_1") (class "Default")
      (node (ref "IC4") (pin "43") (pinfunction "PB7/I2C1_SDA/USART1_RX/TIM4_CH2_43") (pintype "bidirectional"))
      (node (ref "SW1") (pin "3") (pinfunction "3_3") (pintype "passive"))
      (node (ref "SW1") (pin "4") (pinfunction "4_4") (pintype "passive"))
    )
    (net (code "95") (name "SW_2") (class "Default")
      (node (ref "IC4") (pin "42") (pinfunction "PB6/I2C1_SCL/USART1_TX/TIM4_CH1_42") (pintype "bidirectional"))
      (node (ref "SW2") (pin "3") (pinfunction "3_3") (pintype "passive"))
      (node (ref "SW2") (pin "4") (pinfunction "4_4") (pintype "passive"))
    )
    (net (code "96") (name "TIMBRE_ATT") (class "Default")
      (node (ref "C53") (pin "1") (pinfunction "1_1") (pintype "passive"))
      (node (ref "IC4") (pin "16") (pinfunction "PA6/SPI1_MISO/I2S1_MCK/TIM3_CH1/ADC_IN6/DAC2_OUT1_16") (pintype "bidirectional"))
      (node (ref "R42") (pin "P$2") (pinfunction "S_P$2") (pintype "passive"))
    )
    (net (code "97") (name "TIMBRE_POT") (class "Default")
      (node (ref "C32") (pin "1") (pinfunction "1_1") (pintype "passive"))
      (node (ref "IC4") (pin "13") (pinfunction "PA3/SPI3_MOSI/I2S3_SD/USART2_RX/TIM2_CH4/TIM5_CH4/ADC_IN3_13") (pintype "bidirectional"))
      (node (ref "R7") (pin "P$2") (pinfunction "S_P$2") (pintype "passive"))
    )
    (net (code "98") (name "TX") (class "Default")
      (node (ref "IC4") (pin "45") (pinfunction "PB8/SPI2_SCK/I2S2_CK/I2C1_SCL/USART3_TX/CAN_RX/TIM4_CH3_45") (pintype "bidirectional"))
      (node (ref "R10") (pin "2") (pinfunction "2_2") (pintype "passive"))
    )
    (net (code "99") (name "VCC") (class "Default")
      (node (ref "C37") (pin "1") (pinfunction "1_1") (pintype "passive"))
      (node (ref "C4") (pin "+") (pinfunction "+_+") (pintype "passive"))
      (node (ref "IC8") (pin "8") (pinfunction "V+_8") (pintype "power_in"))
      (node (ref "L2") (pin "1") (pinfunction "1_1") (pintype "passive"))
    )
    (net (code "100") (name "VEE") (class "Default")
      (node (ref "C45") (pin "2") (pinfunction "2_2") (pintype "passive"))
      (node (ref "C5") (pin "-") (pinfunction "-_-") (pintype "passive"))
      (node (ref "IC8") (pin "4") (pinfunction "V-_4") (pintype "power_in"))
      (node (ref "L3") (pin "1") (pinfunction "1_1") (pintype "passive"))
      (node (ref "R37") (pin "1") (pinfunction "1_1") (pintype "passive"))
    )
    (net (code "101") (name "unconnected-(IC2-SOUT-Pad22)") (class "Default")
      (node (ref "IC2") (pin "22") (pinfunction "SOUT_22") (pintype "bidirectional"))
    )
    (net (code "102") (name "unconnected-(IC4-PA15{slash}SPI1_NSS{slash}I2S1_WS{slash}SPI3_NSS{slash}I2S3_WS{slash}I2C1_SCL{slash}TIM2_CH1_ETR{slash}JTDI-Pad38)") (class "Default")
      (node (ref "IC4") (pin "38") (pinfunction "PA15/SPI1_NSS/I2S1_WS/SPI3_NSS/I2S3_WS/I2C1_SCL/TIM2_CH1_ETR/JTDI_38") (pintype "bidirectional"))
    )
    (net (code "103") (name "unconnected-(IC4-PB3{slash}SPI1_SCK{slash}I2S1_CK{slash}SPI3_SCK{slash}I2S3_CK{slash}USART2_TX{slash}TIM2_CH2{slash}JTDO{slash}SPI3_SCK{slash}JTDO-Pad39)") (class "Default")
      (node (ref "IC4") (pin "39") (pinfunction "PB3/SPI1_SCK/I2S1_CK/SPI3_SCK/I2S3_CK/USART2_TX/TIM2_CH2/JTDO/SPI3_SCK/JTDO_39") (pintype "bidirectional"))
    )
    (net (code "104") (name "unconnected-(IC4-PB4{slash}SPI1_MISO{slash}I2S1_MCK{slash}SPI3_MISO{slash}I2S3_MCK{slash}USART2_RX{slash}TIM3_CH1{slash}NJTRST-Pad40)") (class "Default")
      (node (ref "IC4") (pin "40") (pinfunction "PB4/SPI1_MISO/I2S1_MCK/SPI3_MISO/I2S3_MCK/USART2_RX/TIM3_CH1/NJTRST_40") (pintype "bidirectional"))
    )
    (net (code "105") (name "unconnected-(IC4-PB5{slash}SPI1_MOSI{slash}I2S1_SD{slash}SPI3_MOSI{slash}I2S3_SD{slash}I2C1_SMBAI{slash}USART2_CK{slash}TIM3_CH2-Pad41)") (class "Default")
      (node (ref "IC4") (pin "41") (pinfunction "PB5/SPI1_MOSI/I2S1_SD/SPI3_MOSI/I2S3_SD/I2C1_SMBAI/USART2_CK/TIM3_CH2_41") (pintype "bidirectional"))
    )
    (net (code "106") (name "unconnected-(IC4-PC13{slash}TIMESTAMP{slash}RTC_TAMPER1-Pad2)") (class "Default")
      (node (ref "IC4") (pin "2") (pinfunction "PC13/TIMESTAMP/RTC_TAMPER1_2") (pintype "bidirectional"))
    )
    (net (code "107") (name "unconnected-(IC4-PC14{slash}OSC32_IN-Pad3)") (class "Default")
      (node (ref "IC4") (pin "3") (pinfunction "PC14/OSC32_IN_3") (pintype "bidirectional"))
    )
    (net (code "108") (name "unconnected-(IC4-PC15{slash}OSC32_OUT-Pad4)") (class "Default")
      (node (ref "IC4") (pin "4") (pinfunction "PC15/OSC32_OUT_4") (pintype "bidirectional"))
    )
    (net (code "109") (name "unconnected-(J9-2-PadP2)") (class "Default")
      (node (ref "J9") (pin "P2") (pinfunction "2_P2") (pintype "passive"))
    )
    (net (code "110") (name "unconnected-(J10-2-PadP2)") (class "Default")
      (node (ref "J10") (pin "P2") (pinfunction "2_P2") (pintype "passive"))
    )
  )
)
